# Bidirectional_Amp.net
KiCad netlist of a schematic drawn in EAGLE
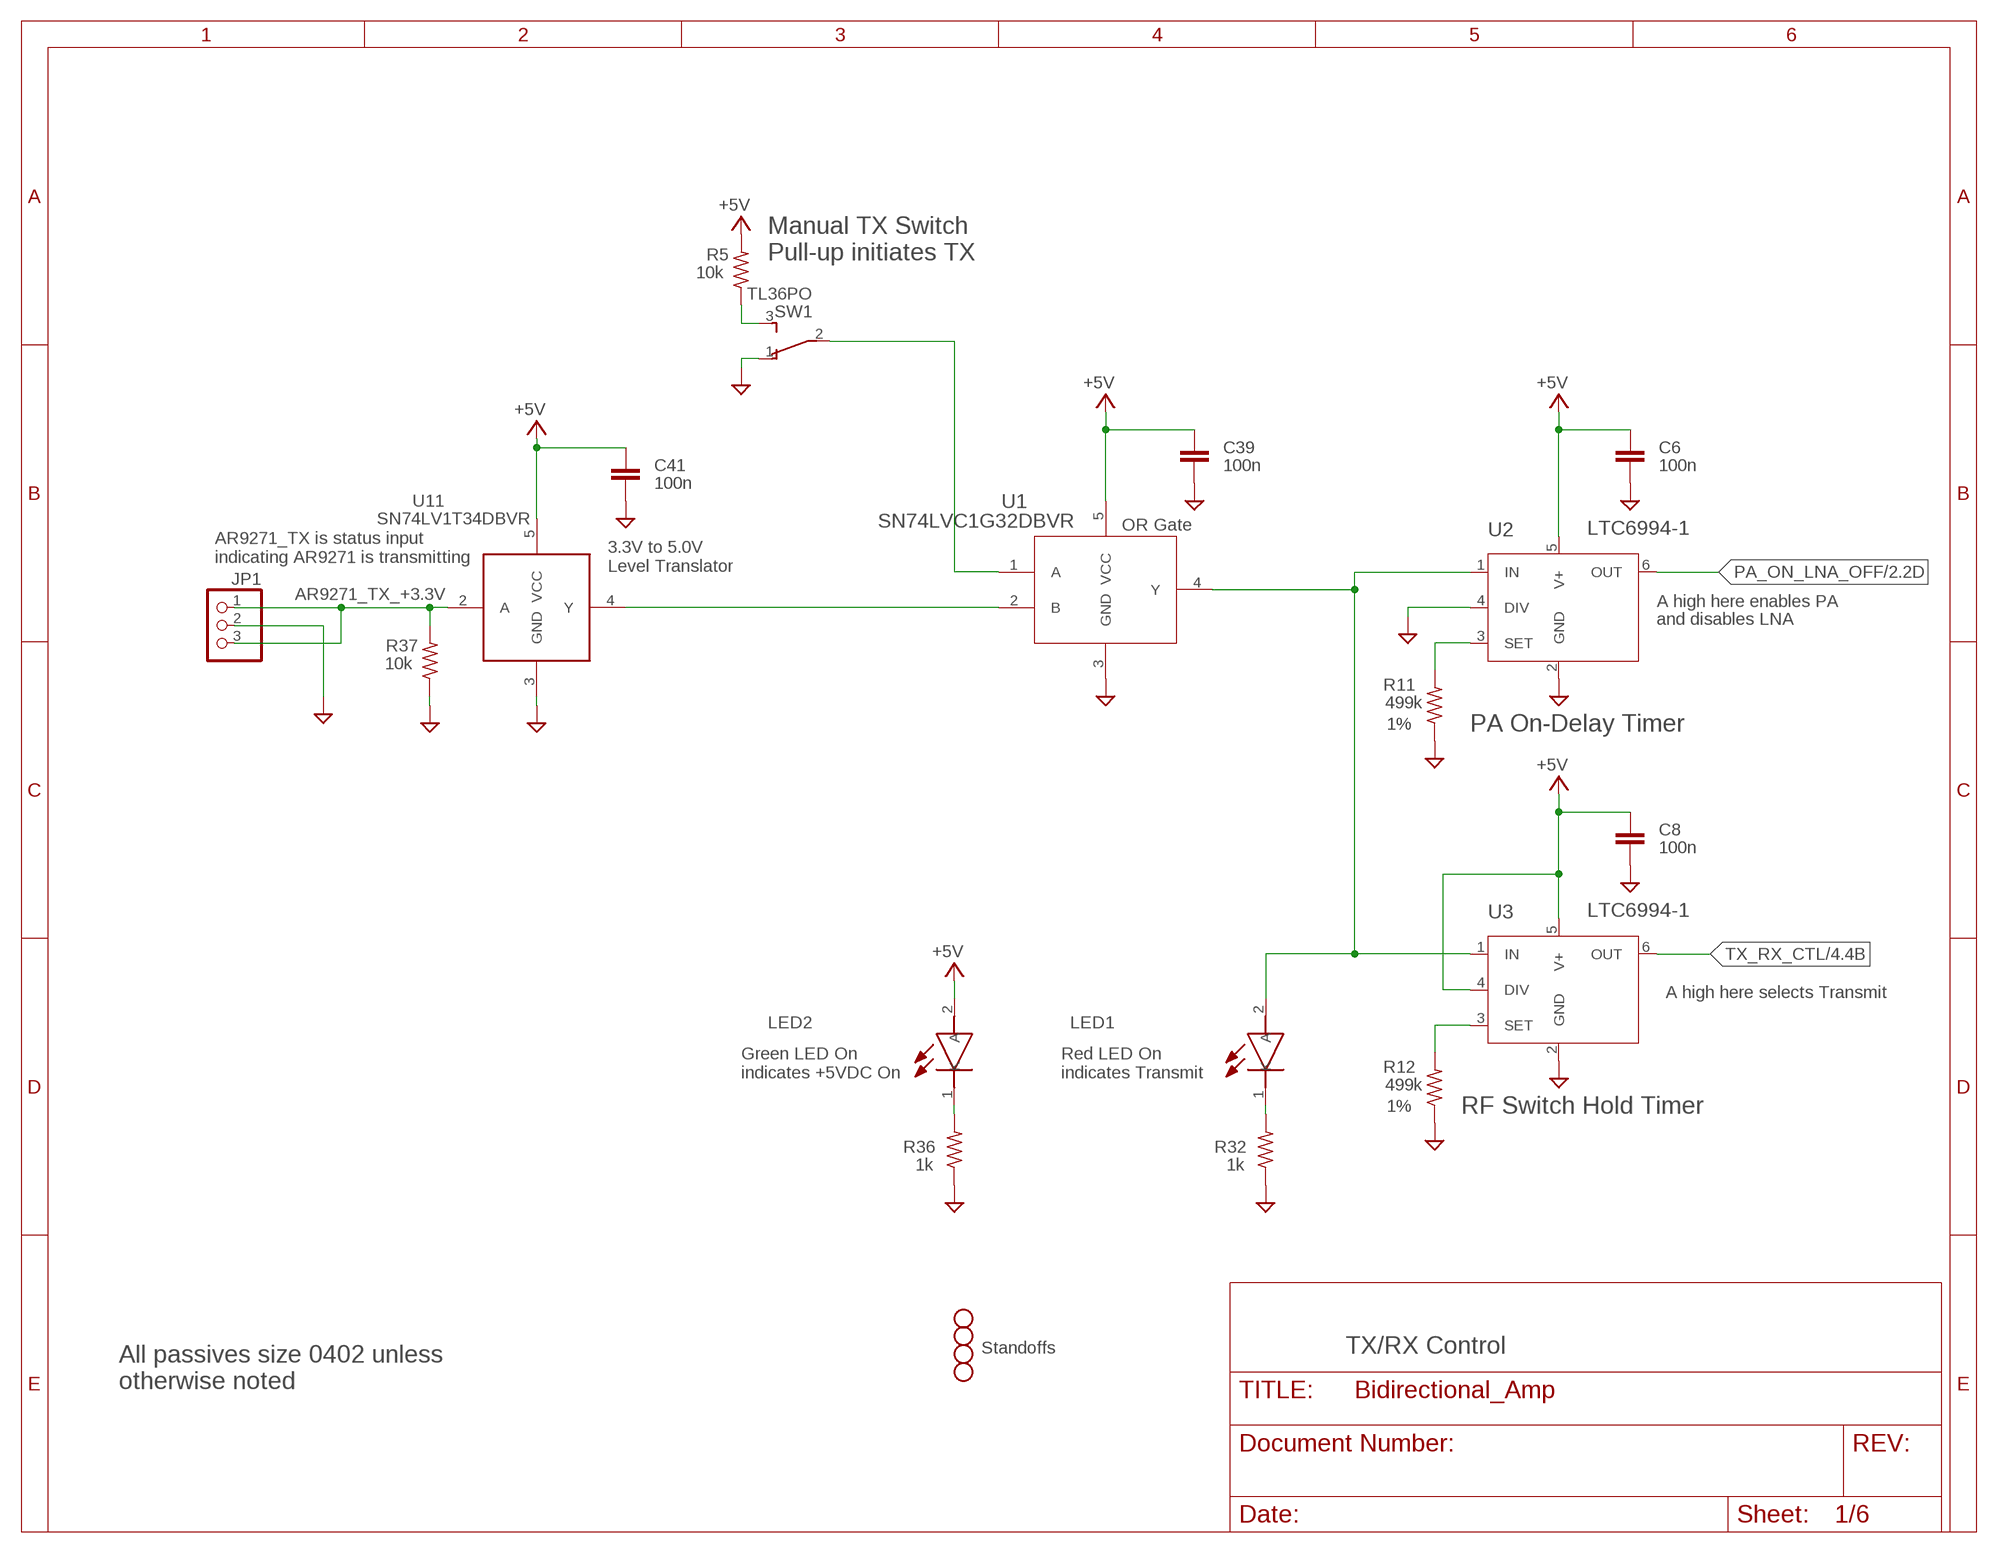
[diagram p0: schematic, sheet 1]
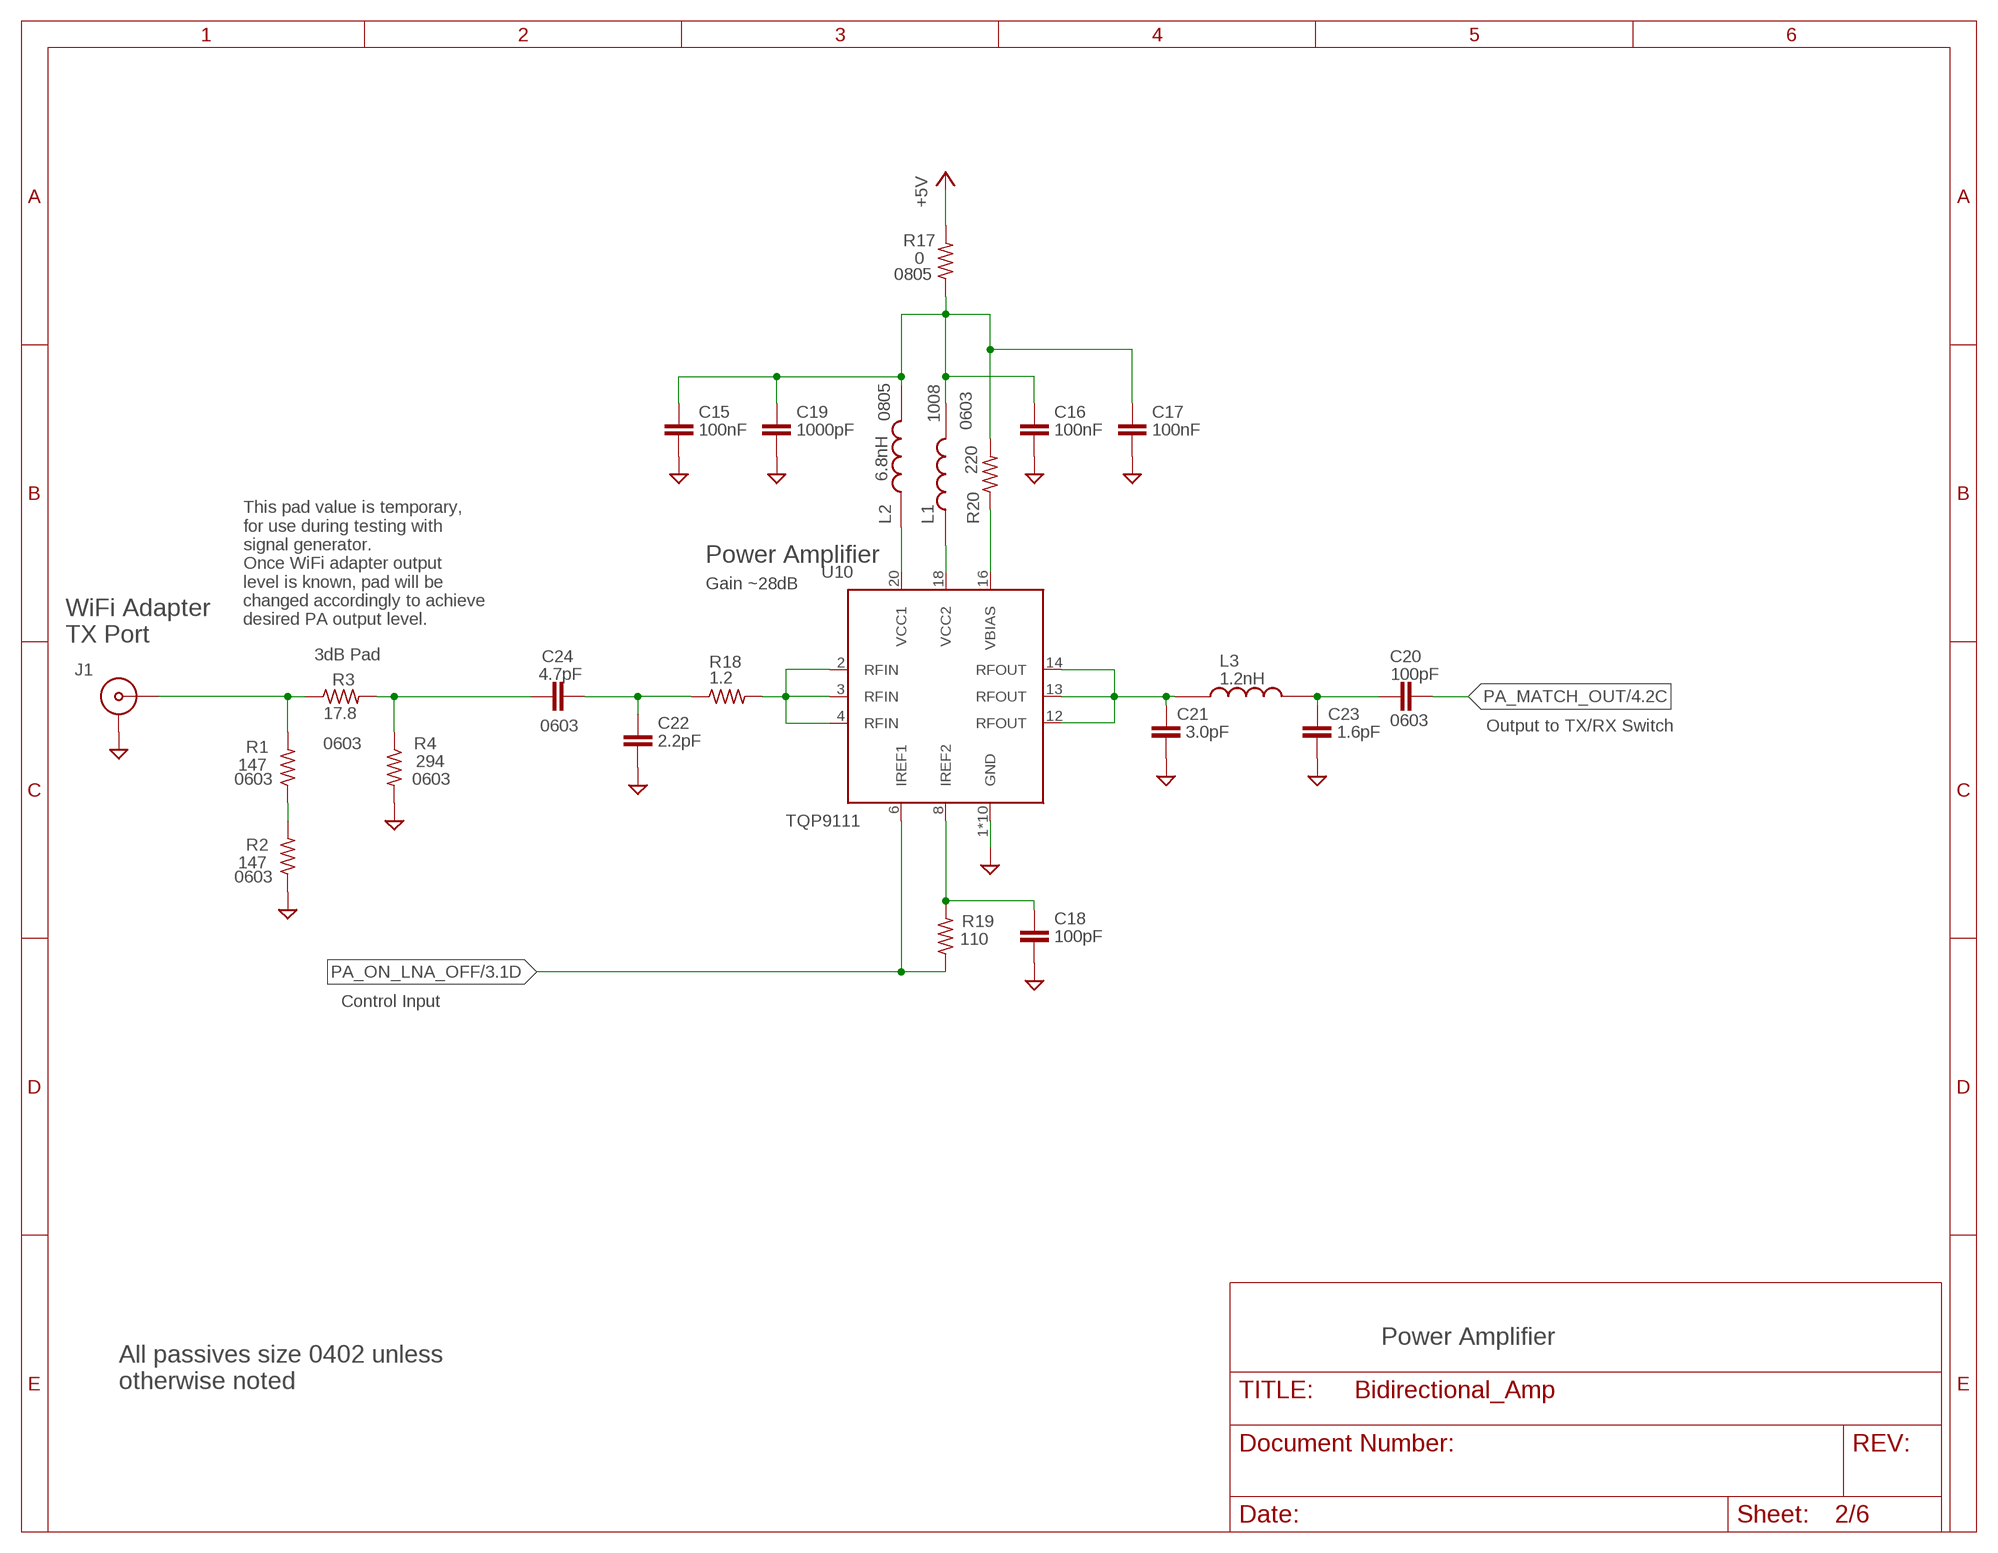
[diagram p1: schematic, sheet 2]
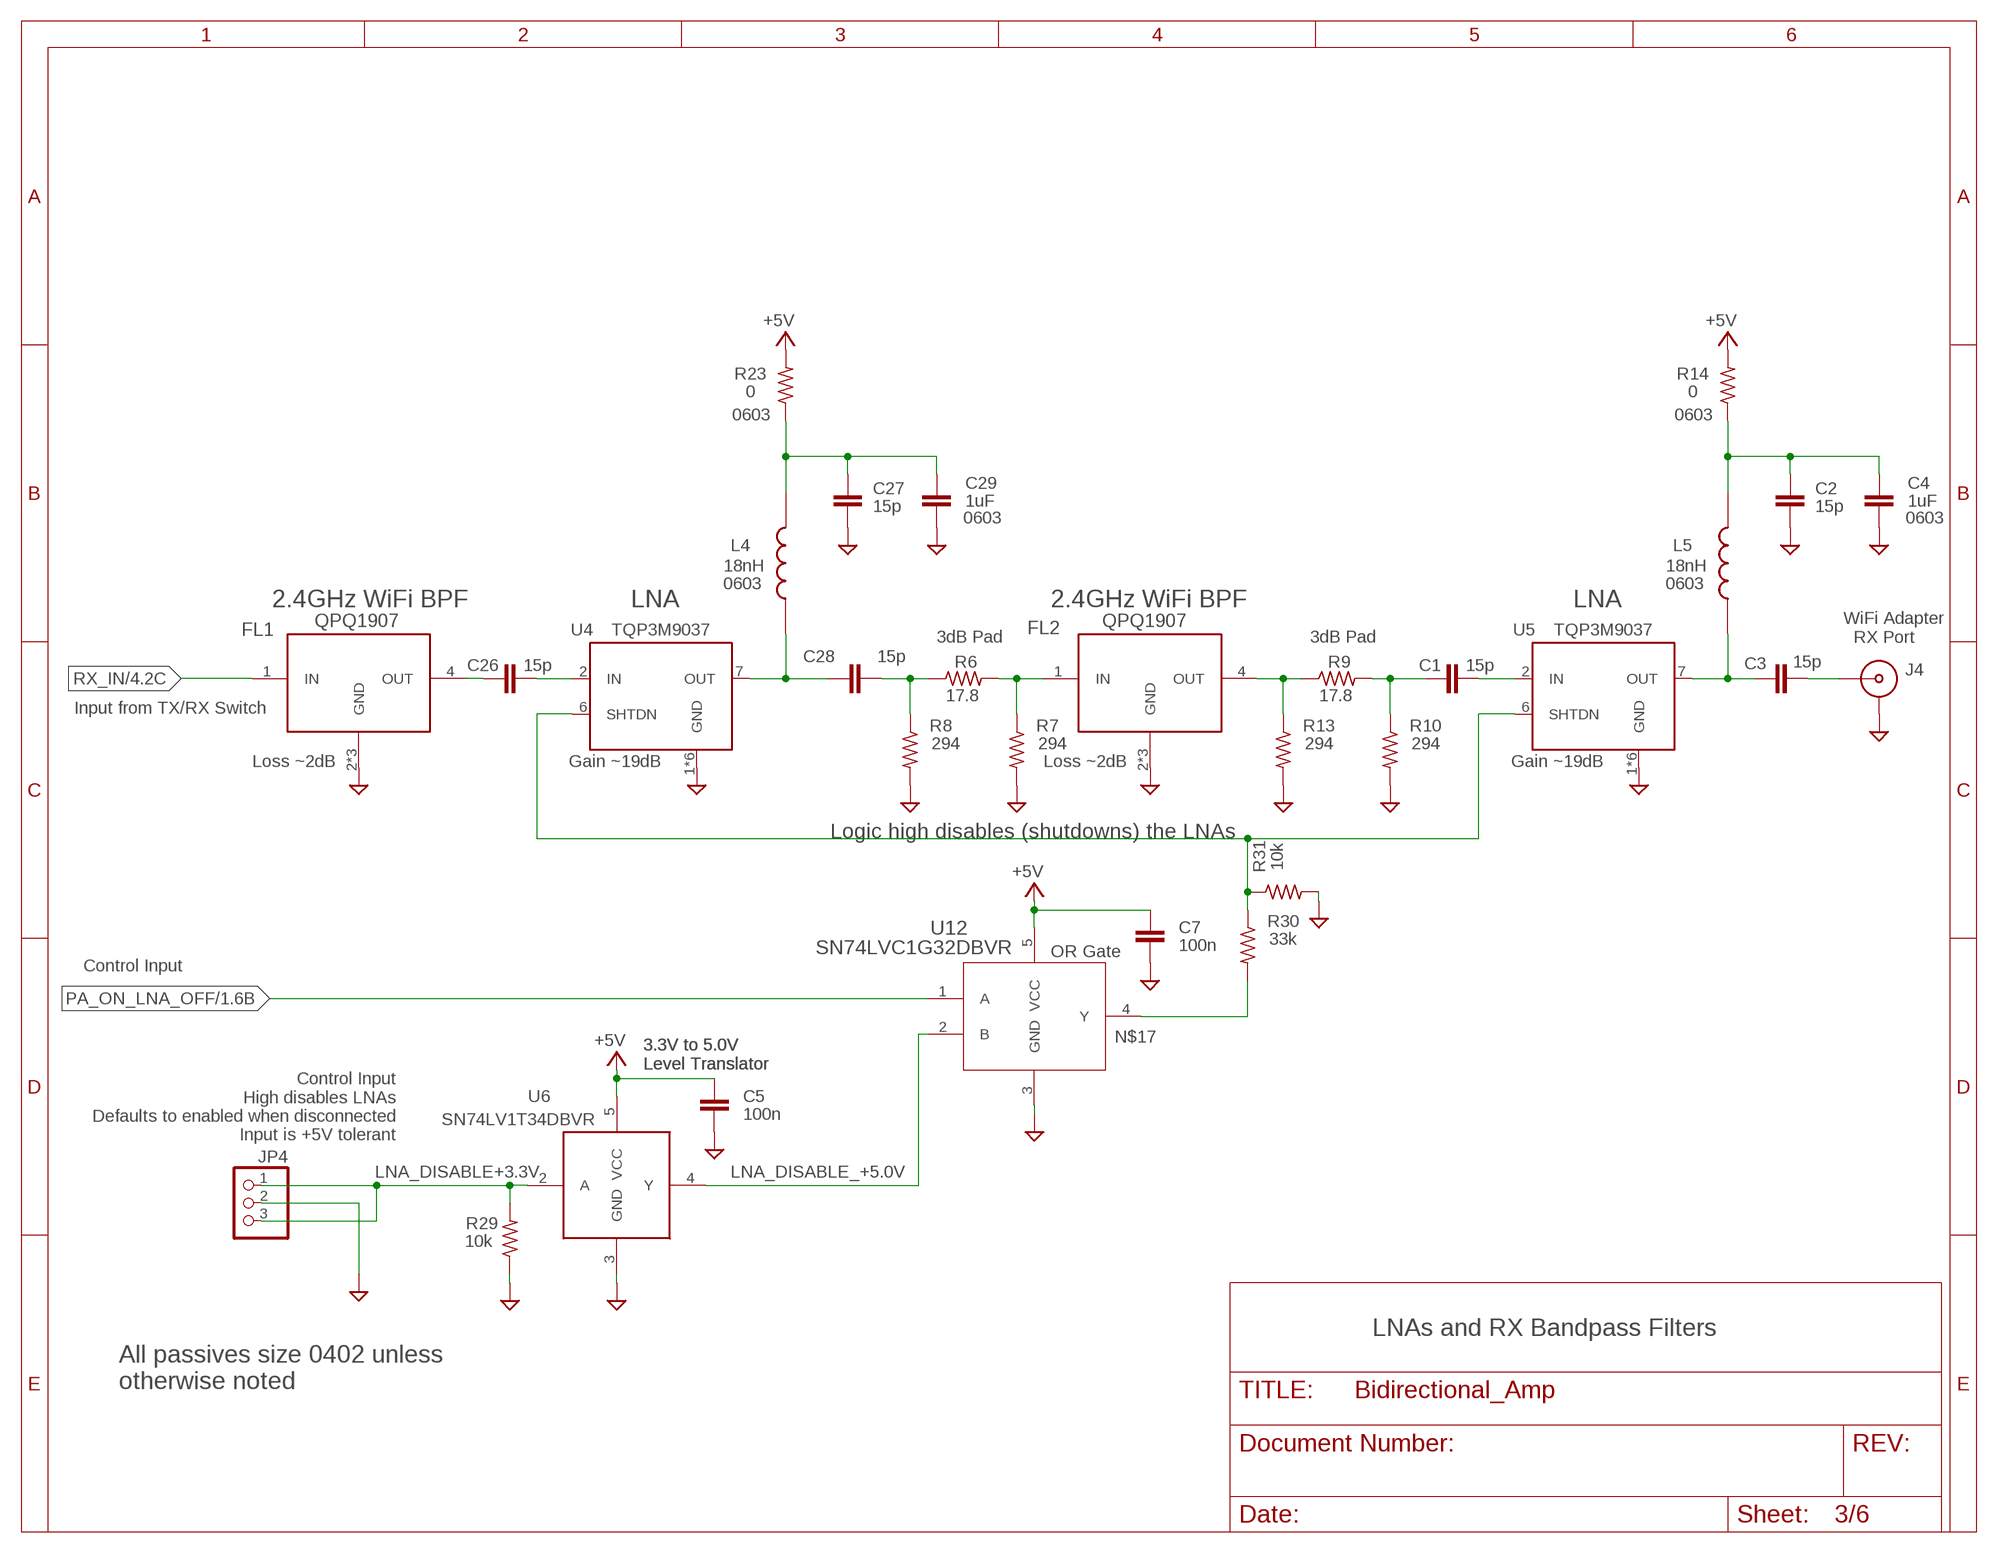
[diagram p2: schematic, sheet 3]
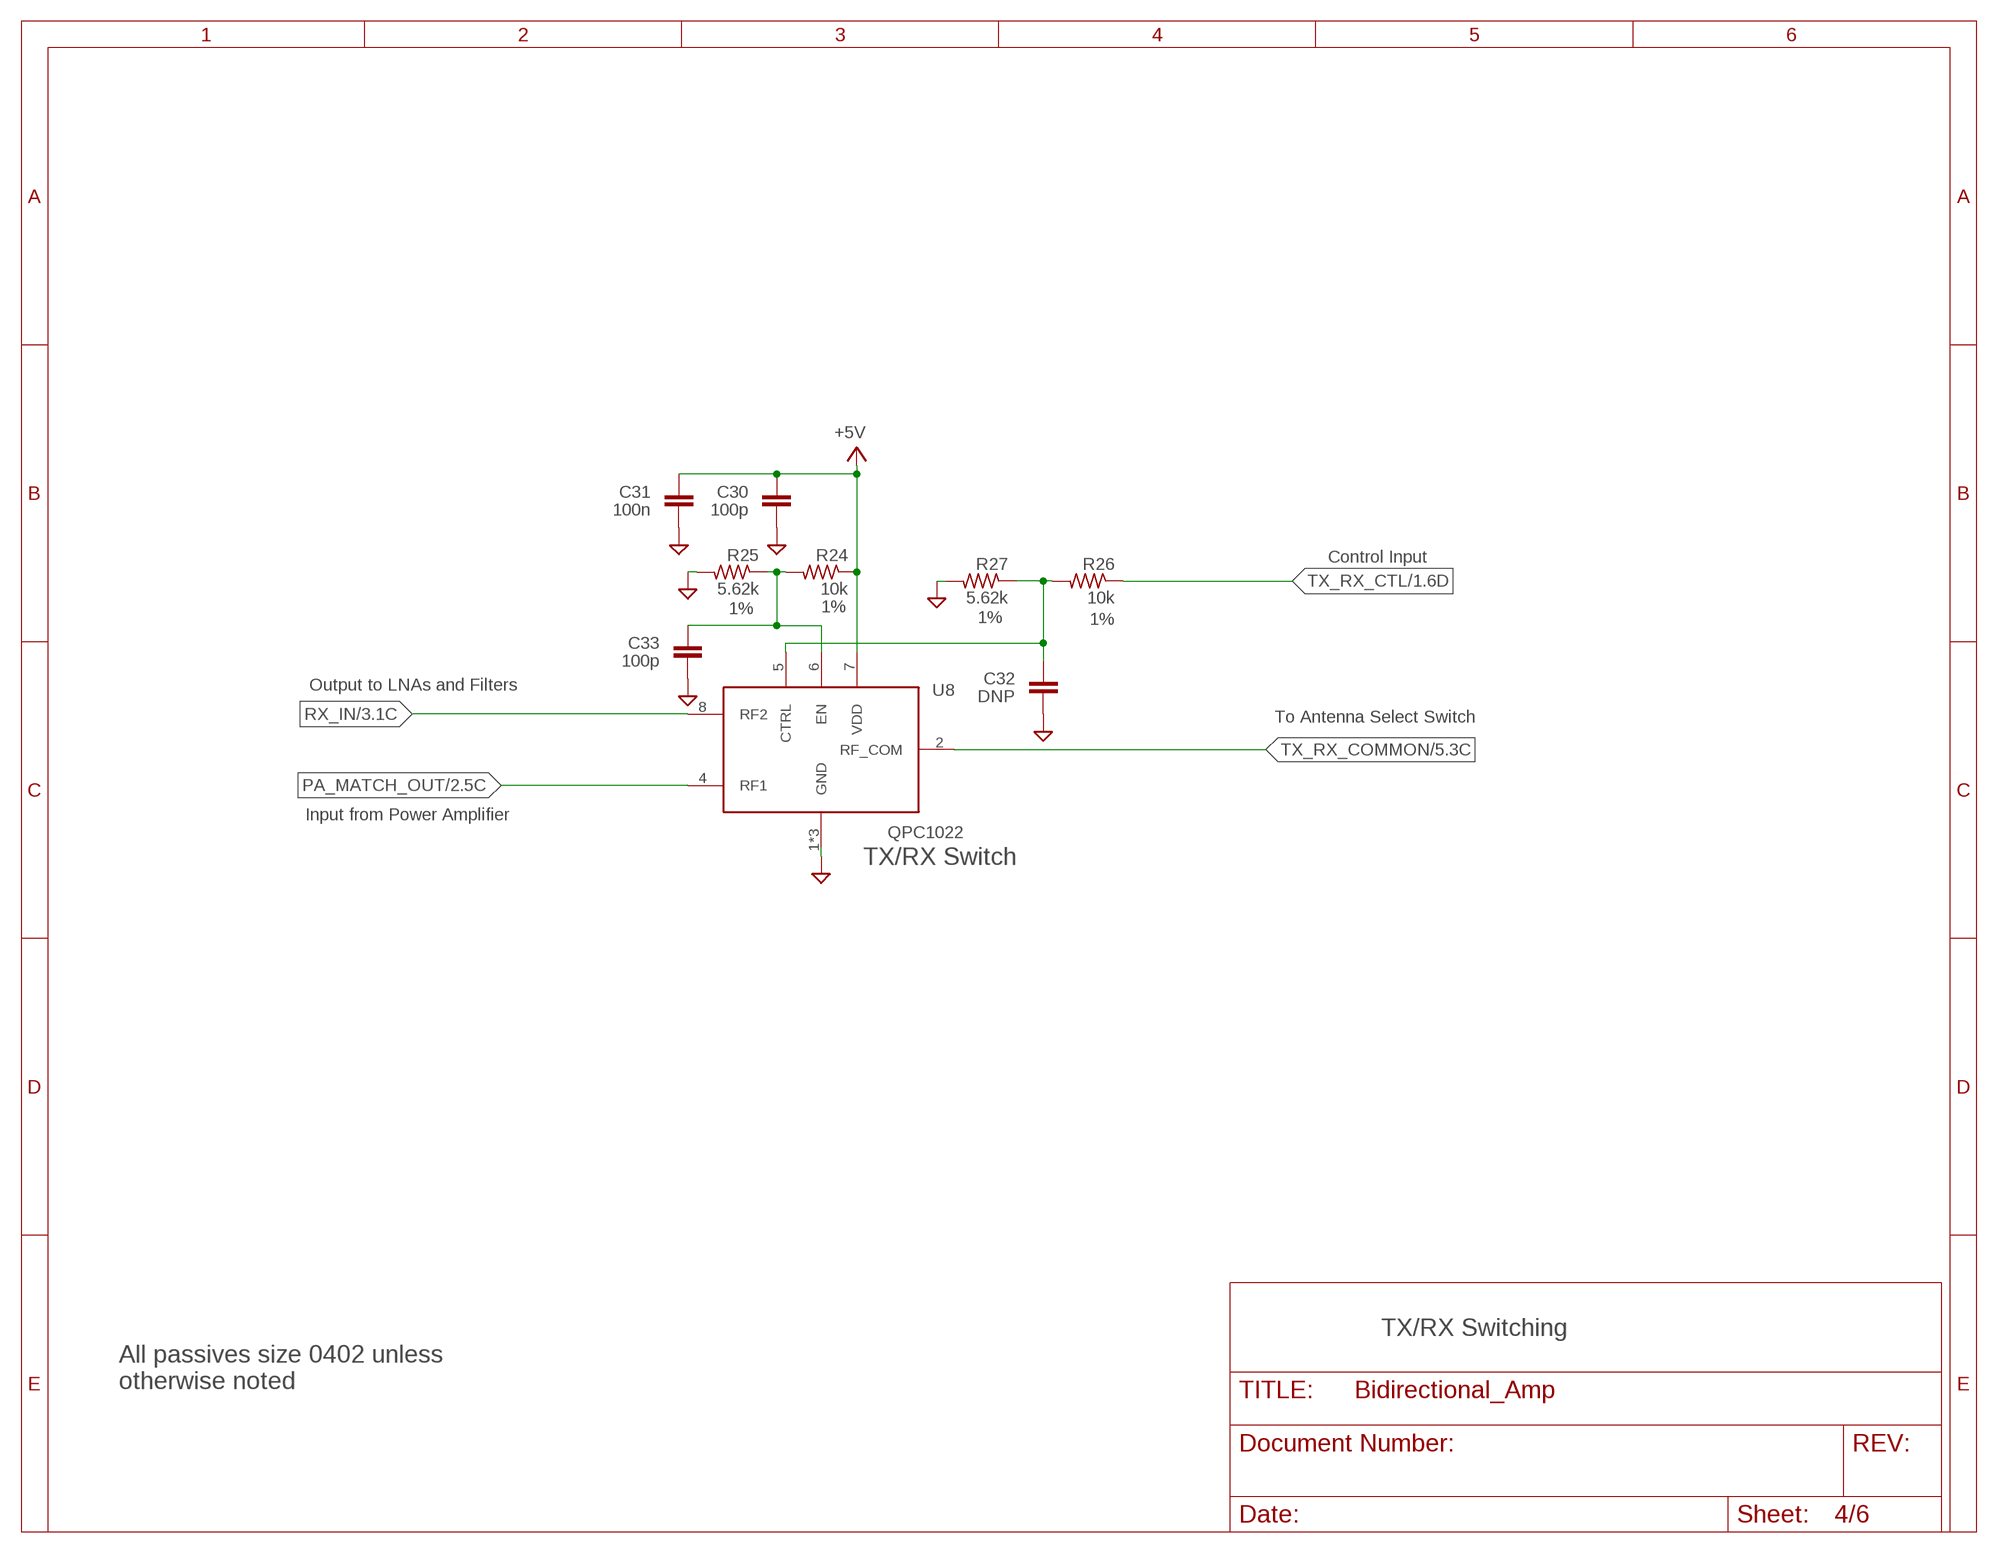
[diagram p3: schematic, sheet 4]
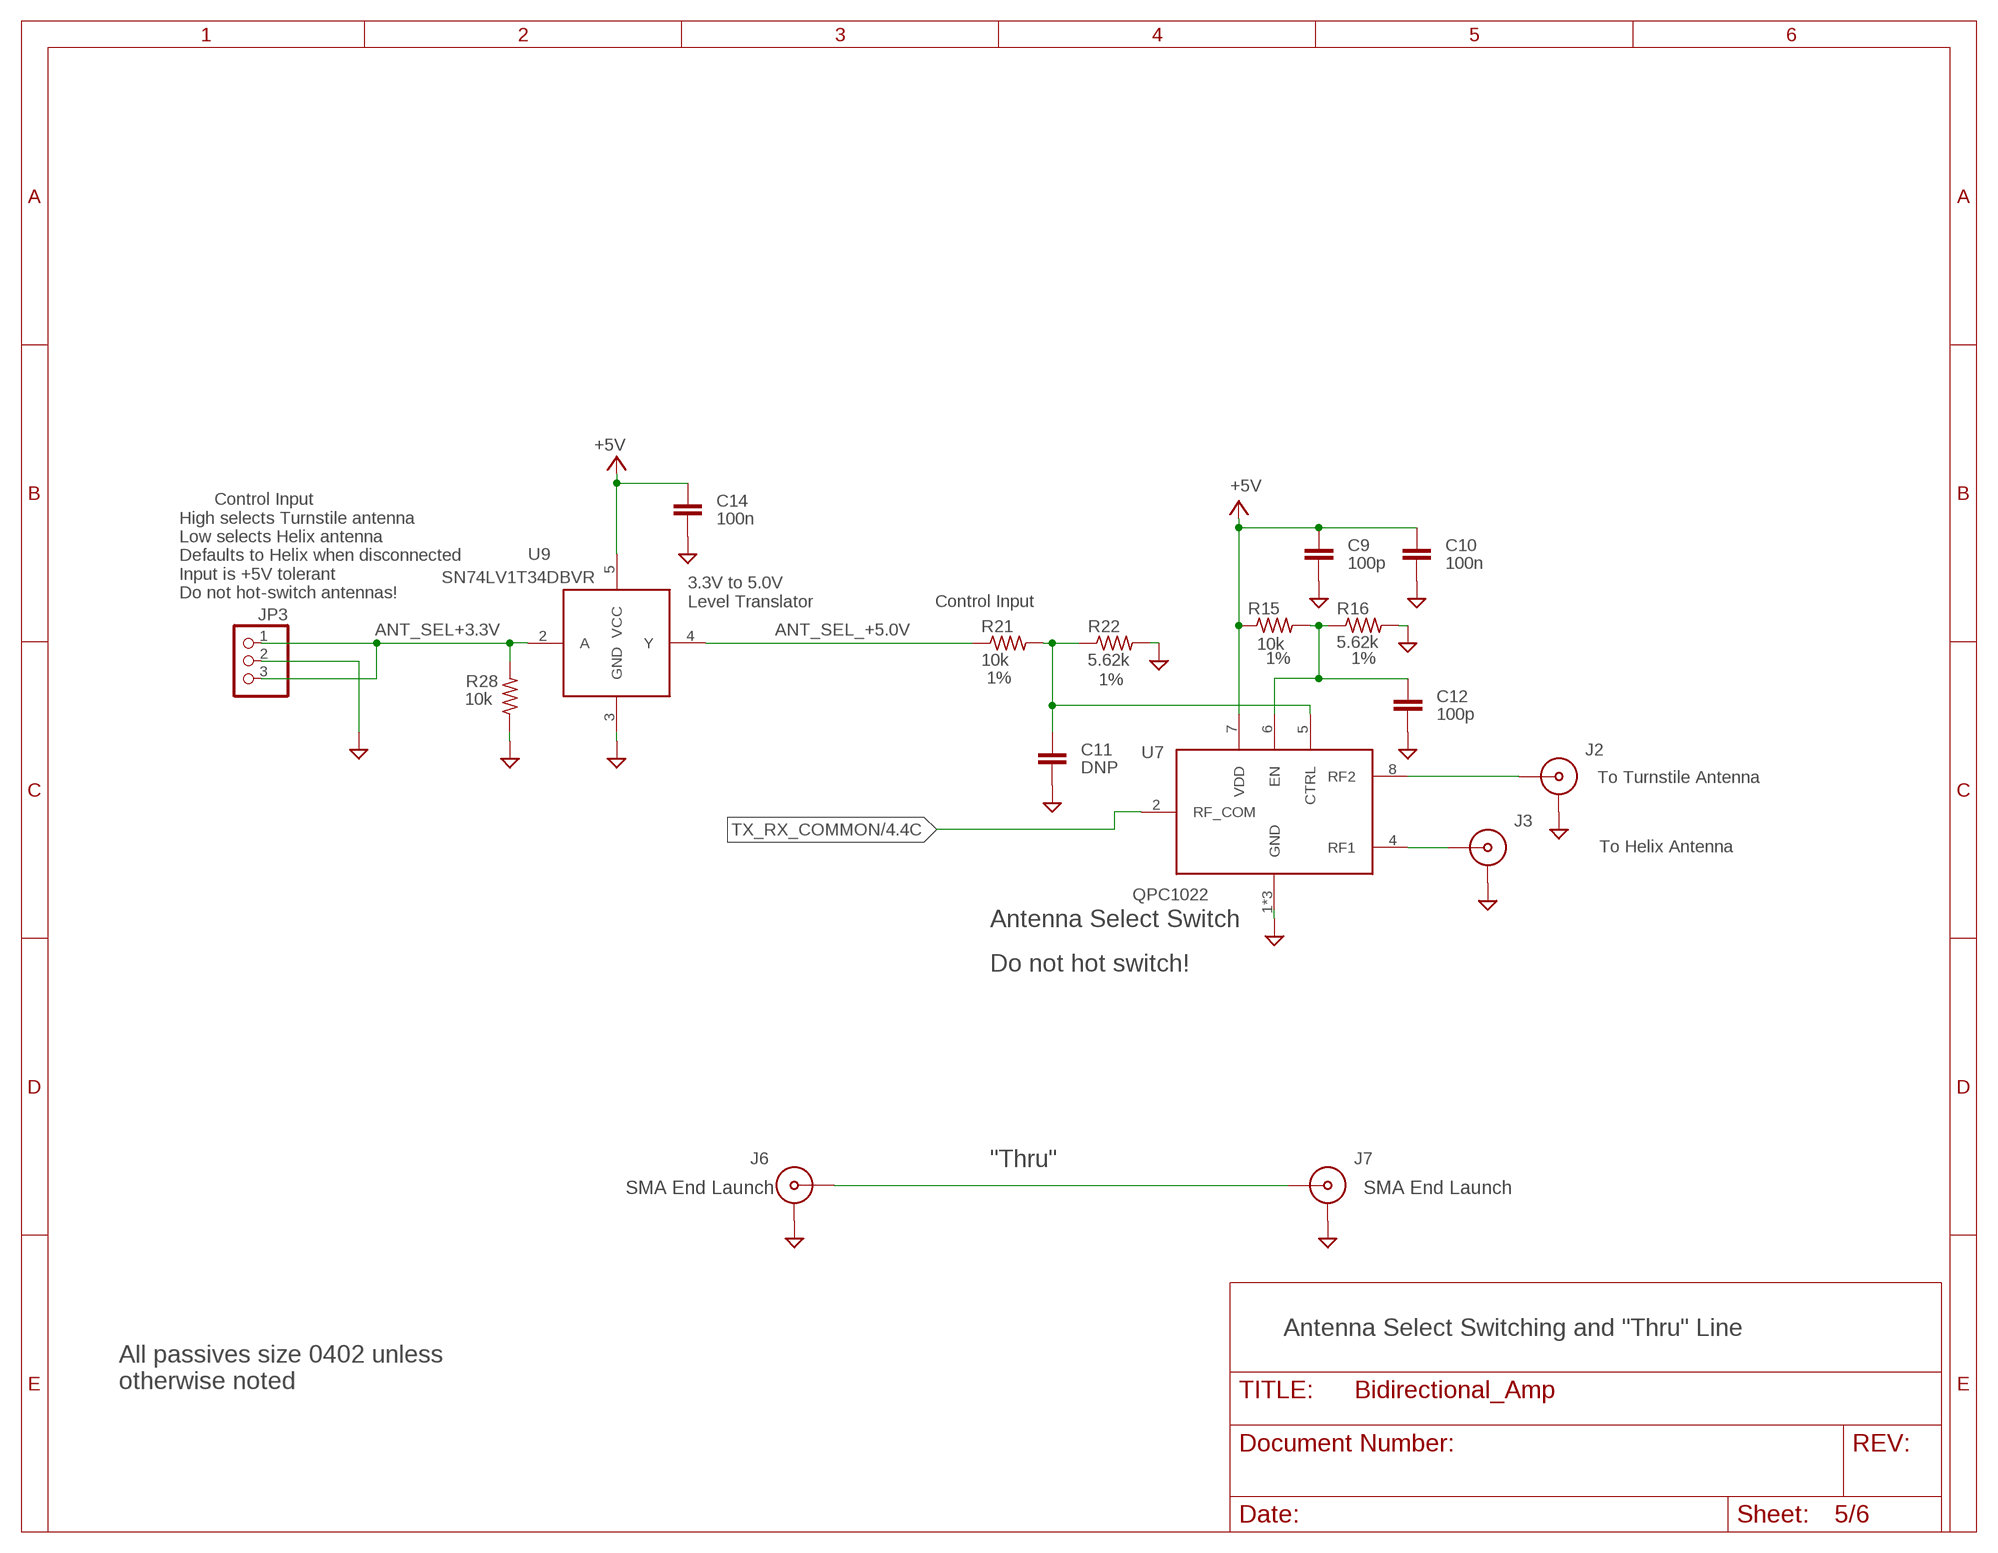
[diagram p4: schematic, sheet 5]
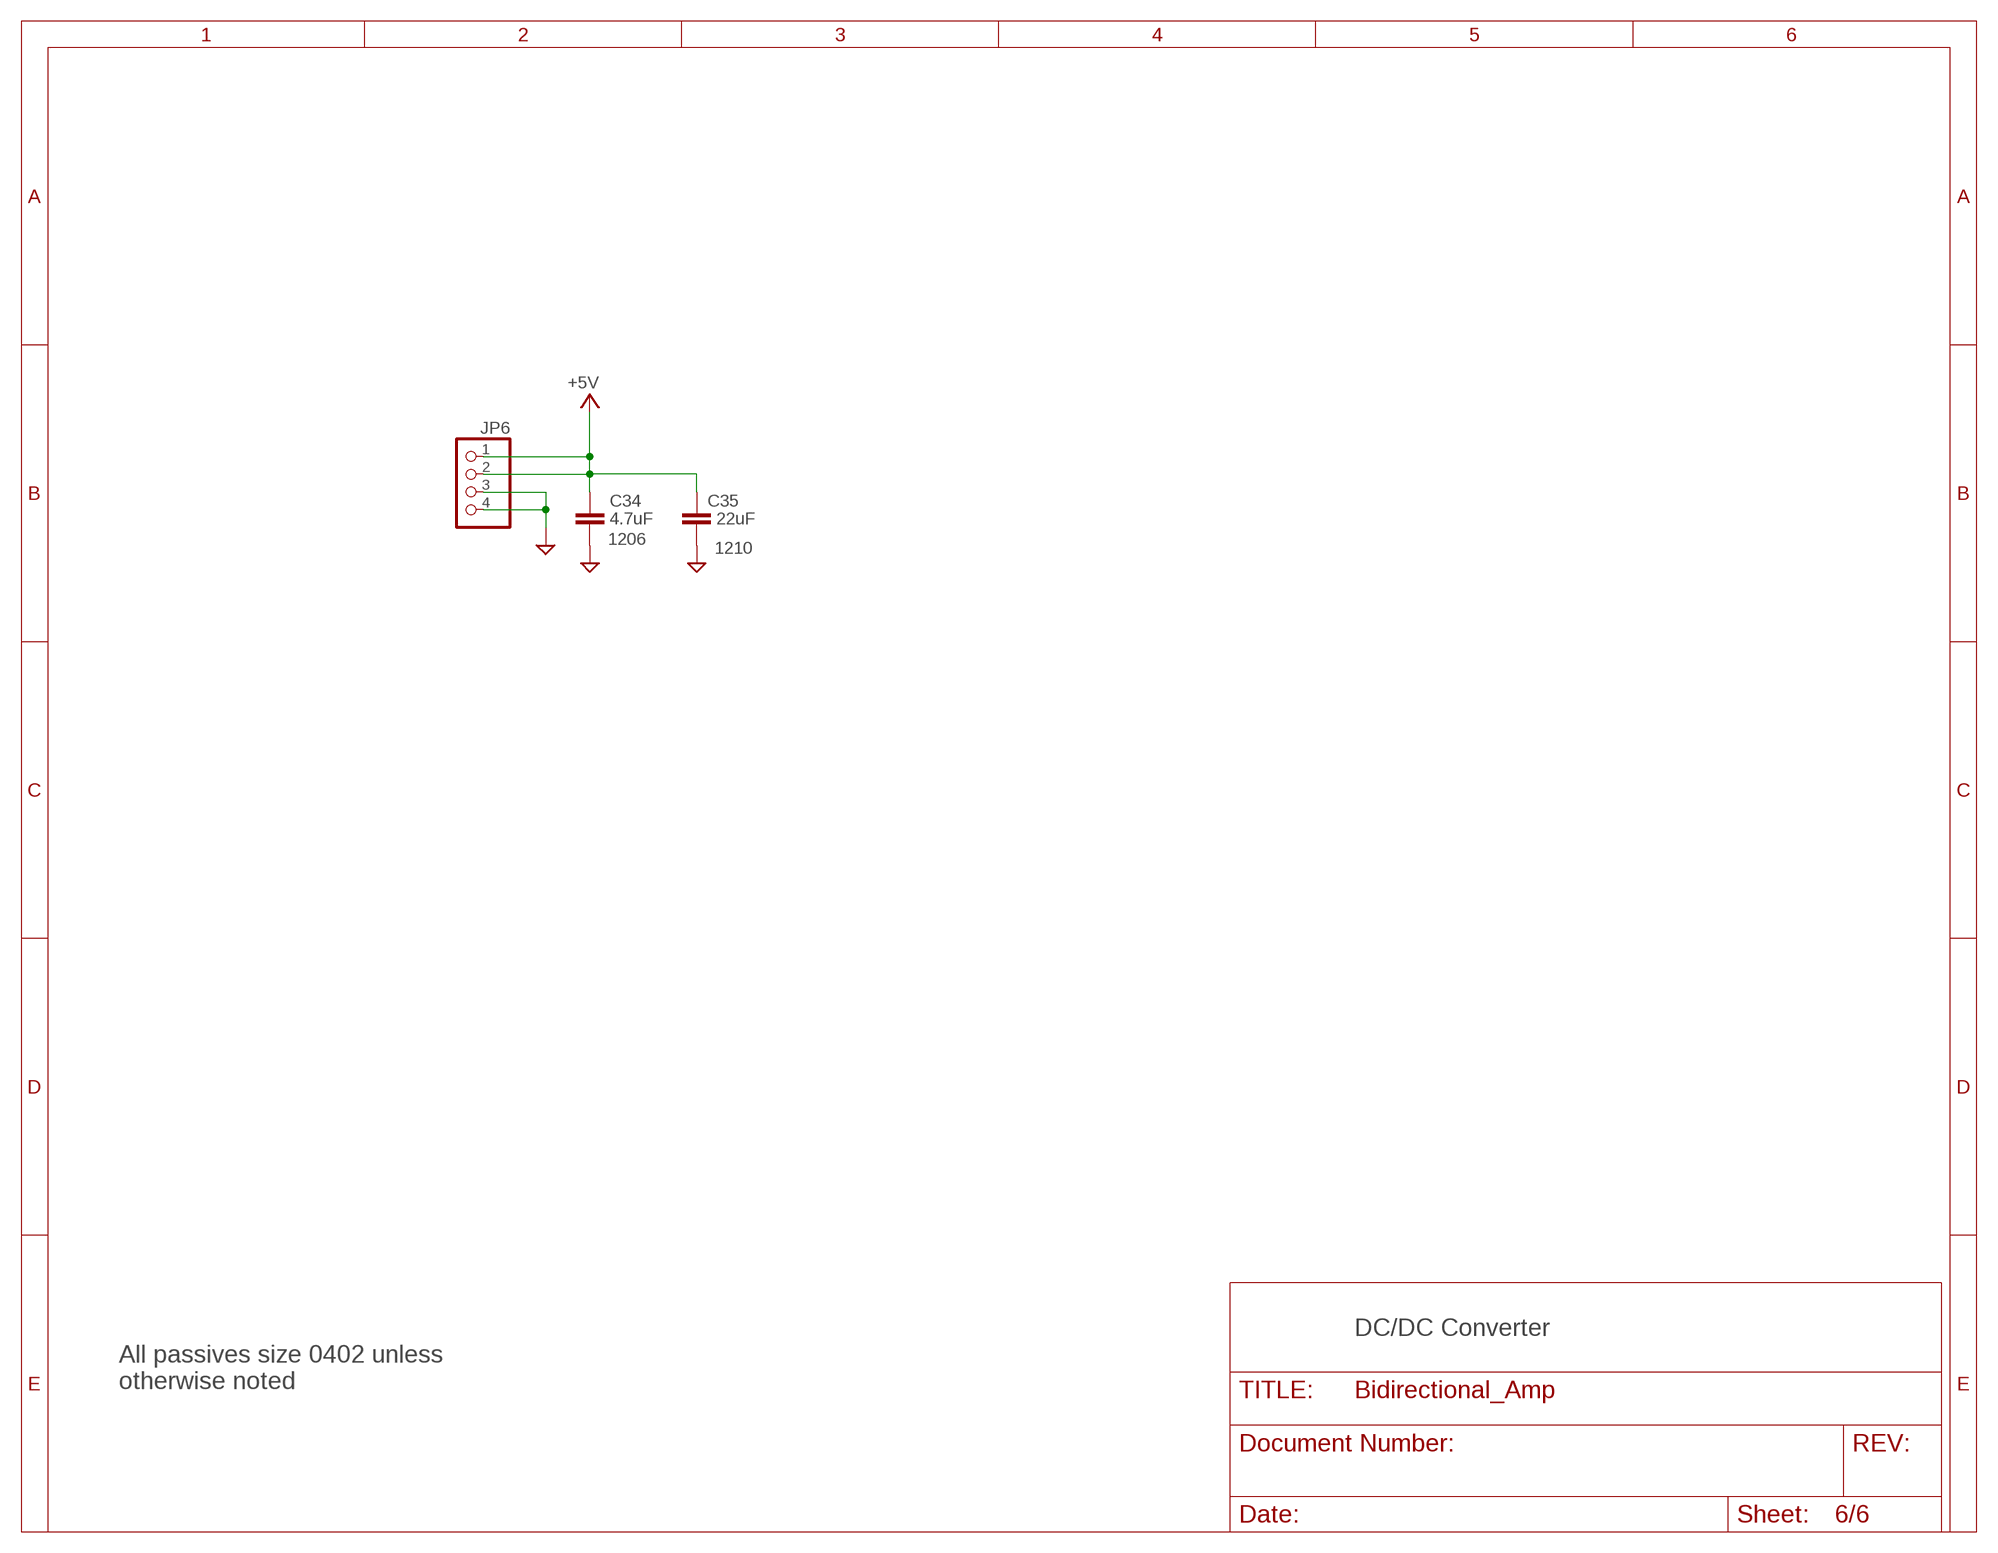
[diagram p5: schematic, sheet 6]

(export (version "E")
  (design (tool "Eeschema 10.0.6"))
  (components
    (comp (ref "C34")
      (value "4.7uF")
      (footprint "eagle-import:C1206")
      (fields
        (field (name "MFR") "Murata")
        (field (name "MPN") "GCJ31CR71C475KA01L")
        (field (name "VOLTAGE") "16V")
      )
      (libsource (lib "eagle-import") (part "rcl_334_C-EUC1206"))
    )
    (comp (ref "C35")
      (value "22uF")
      (footprint "eagle-import:C1210")
      (fields (field (name "MFR") "Murata") (field (name "MPN") "GCJ32ER71C226KE01L"))
      (libsource (lib "eagle-import") (part "rcl_334_C-EUC1210"))
    )
    (comp (ref "JP6")
      (value "PINHD-1X4")
      (footprint "eagle-import:1X04")
      (libsource (lib "eagle-import") (part "PINHD-1X4"))
    )
    (comp (ref "C1")
      (value "15p")
      (footprint "eagle-import:.0402-C-NOSILK")
      (fields (field (name "MFR") "Murata") (field (name "MPN") "GJM1555C1H150JB01D "))
      (libsource (lib "eagle-import") (part "C-EU0402-C-NOSILK"))
    )
    (comp (ref "C2")
      (value "15p")
      (footprint "eagle-import:.0402-B-NOSILK")
      (fields (field (name "MFR") "Murata") (field (name "MPN") "GJM1555C1H150JB01D "))
      (libsource (lib "eagle-import") (part "C-EU0402-B-NOSILK"))
    )
    (comp (ref "C3")
      (value "15p")
      (footprint "eagle-import:.0402-C-NOSILK")
      (fields (field (name "MFR") "Murata") (field (name "MPN") "GJM1555C1H150JB01D "))
      (libsource (lib "eagle-import") (part "C-EU0402-C-NOSILK"))
    )
    (comp (ref "C4")
      (value "1uF")
      (footprint "eagle-import:.0603-B-NOSILK")
      (fields (field (name "MFR") "KEMET") (field (name "MPN") "C0603X105M4RACAUTO "))
      (libsource (lib "eagle-import") (part "C-EU0603-B-NOSILK"))
    )
    (comp (ref "C5")
      (value "100n")
      (footprint "eagle-import:.0402-B-NOSILK")
      (fields (field (name "MFR") "TDK Corporation") (field (name "MPN") "CGA2B1X7R1C104K050BC"))
      (libsource (lib "eagle-import") (part "C-EU0402-B-NOSILK"))
    )
    (comp (ref "C7")
      (value "100n")
      (footprint "eagle-import:.0402-B-NOSILK")
      (fields (field (name "MFR") "TDK") (field (name "MPN") "CGA2B1X7R1C104K050BC"))
      (libsource (lib "eagle-import") (part "C-EU0402-B-NOSILK"))
    )
    (comp (ref "C26")
      (value "15p")
      (footprint "eagle-import:.0402-C-NOSILK")
      (fields (field (name "MFR") "Murata") (field (name "MPN") "GJM1555C1H150JB01D "))
      (libsource (lib "eagle-import") (part "C-EU0402-C-NOSILK"))
    )
    (comp (ref "C27")
      (value "15p")
      (footprint "eagle-import:.0402-B-NOSILK")
      (fields (field (name "MFR") "Murata") (field (name "MPN") "GJM1555C1H150JB01D "))
      (libsource (lib "eagle-import") (part "C-EU0402-B-NOSILK"))
    )
    (comp (ref "C28")
      (value "15p")
      (footprint "eagle-import:.0402-C-NOSILK")
      (fields (field (name "MFR") "Murata") (field (name "MPN") "GJM1555C1H150JB01D "))
      (libsource (lib "eagle-import") (part "C-EU0402-C-NOSILK"))
    )
    (comp (ref "C29")
      (value "1uF")
      (footprint "eagle-import:.0603-B-NOSILK")
      (fields (field (name "MFR") "KEMET") (field (name "MPN") "C0603X105M4RACAUTO "))
      (libsource (lib "eagle-import") (part "C-EU0603-B-NOSILK"))
    )
    (comp (ref "FL1")
      (value "QPQ1907")
      (footprint "eagle-import:FIL_B39162B9417K610")
      (fields (field (name "MFR") "Qorvo") (field (name "MPN") "885071-A") (field (name "MPN_1") "QPQ1907"))
      (libsource (lib "eagle-import") (part "QPQ1907"))
    )
    (comp (ref "FL2")
      (value "QPQ1907")
      (footprint "eagle-import:FIL_B39162B9417K610")
      (fields (field (name "MFR") "Qorvo") (field (name "MPN") "885071-A") (field (name "MPN_1") "QPQ1907"))
      (libsource (lib "eagle-import") (part "QPQ1907"))
    )
    (comp (ref "J4")
      (value "142-0701-851_ALT")
      (footprint "eagle-import:142-0701-851")
      (fields (field (name "MFR") "Cinch") (field (name "MPN") "142-0701-851"))
      (libsource (lib "eagle-import") (part "142-0701-851_ALT"))
    )
    (comp (ref "JP4")
      (value "PINHD-1X3")
      (footprint "eagle-import:1X03")
      (fields (field (name "MFR") "Molex") (field (name "MPN") "22-23-2031"))
      (libsource (lib "eagle-import") (part "PINHD-1X3"))
    )
    (comp (ref "L4")
      (value "68nH")
      (footprint "eagle-import:0603CS-68NXJLW")
      (fields
        (field (name "MFR") "COILCRAFT")
        (field (name "MPN") "0603CS-68NXJLW")
        (field (name "MPN_1") "0603CS-18NXJLW")
      )
      (libsource (lib "eagle-import") (part "0603CS-68NXJLW"))
    )
    (comp (ref "L5")
      (value "68nH")
      (footprint "eagle-import:0603CS-68NXJLW")
      (fields
        (field (name "MFR") "COILCRAFT")
        (field (name "MPN") "0603CS-68NXJLW")
        (field (name "MPN_1") "0603CS-18NXJLW")
      )
      (libsource (lib "eagle-import") (part "0603CS-68NXJLW"))
    )
    (comp (ref "R6")
      (value "17.8")
      (footprint "eagle-import:.0402-C-NOSILK")
      (fields (field (name "MFR") "Panasonic") (field (name "MPN") "ERJ-2RKF17R8X"))
      (libsource (lib "eagle-import") (part "R-US_0402-C-NOSILK"))
    )
    (comp (ref "R7")
      (value "294")
      (footprint "eagle-import:.0402-C-NOSILK")
      (fields (field (name "MFR") "Panasonic") (field (name "MPN") "ERJ-2RKF2940X"))
      (libsource (lib "eagle-import") (part "R-US_0402-C-NOSILK"))
    )
    (comp (ref "R8")
      (value "294")
      (footprint "eagle-import:.0402-C-NOSILK")
      (fields (field (name "MFR") "Panasonic") (field (name "MPN") "ERJ-2RKF2940X"))
      (libsource (lib "eagle-import") (part "R-US_0402-C-NOSILK"))
    )
    (comp (ref "R9")
      (value "17.8")
      (footprint "eagle-import:.0402-C-NOSILK")
      (fields (field (name "MFR") "Panasonic") (field (name "MPN") "ERJ-2RKF17R8X"))
      (libsource (lib "eagle-import") (part "R-US_0402-C-NOSILK"))
    )
    (comp (ref "R10")
      (value "294")
      (footprint "eagle-import:.0402-C-NOSILK")
      (fields (field (name "MFR") "Panasonic") (field (name "MPN") "ERJ-2RKF2940X"))
      (libsource (lib "eagle-import") (part "R-US_0402-C-NOSILK"))
    )
    (comp (ref "R13")
      (value "294")
      (footprint "eagle-import:.0402-C-NOSILK")
      (fields (field (name "MFR") "Panasonic") (field (name "MPN") "ERJ-2RKF2940X"))
      (libsource (lib "eagle-import") (part "R-US_0402-C-NOSILK"))
    )
    (comp (ref "R14")
      (value "0")
      (footprint "eagle-import:.0603-B-NOSILK")
      (fields (field (name "MFR") "Panasonic") (field (name "MPN") "ERJ-3GEY0R00V"))
      (libsource (lib "eagle-import") (part "R-US_0603-B-NOSILK"))
    )
    (comp (ref "R23")
      (value "0")
      (footprint "eagle-import:.0603-B-NOSILK")
      (fields (field (name "MFR") "Panasonic") (field (name "MPN") "ERJ-3GEY0R00V"))
      (libsource (lib "eagle-import") (part "R-US_0603-B-NOSILK"))
    )
    (comp (ref "R29")
      (value "10k")
      (footprint "eagle-import:.0402-B-NOSILK")
      (fields (field (name "MFR") "Panasonic") (field (name "MPN") "ERJ-2GEJ103X"))
      (libsource (lib "eagle-import") (part "R-US_0402-B-NOSILK"))
    )
    (comp (ref "R30")
      (value "33k")
      (footprint "eagle-import:.0402-B-NOSILK")
      (fields (field (name "MFR") "Panasonic") (field (name "MPN") "ERJ-2RKF2940X"))
      (libsource (lib "eagle-import") (part "R-US_0402-B-NOSILK"))
    )
    (comp (ref "R31")
      (value "10k")
      (footprint "eagle-import:.0402-B-NOSILK")
      (fields (field (name "MFR") "Panasonic") (field (name "MPN") "ERJ-2RKF2940X"))
      (libsource (lib "eagle-import") (part "R-US_0402-B-NOSILK"))
    )
    (comp (ref "U4")
      (value "TQP3M9037")
      (footprint "eagle-import:DFN8-2X2-WITH-PAD")
      (fields (field (name "MFR") "Qorvo") (field (name "MPN") "TQP3M9037 "))
      (libsource (lib "eagle-import") (part "TQP3M903X"))
    )
    (comp (ref "U5")
      (value "TQP3M9037")
      (footprint "eagle-import:DFN8-2X2-WITH-PAD")
      (fields (field (name "MFR") "Qorvo") (field (name "MPN") "TQP3M9037 "))
      (libsource (lib "eagle-import") (part "TQP3M903X"))
    )
    (comp (ref "U6")
      (value "SN74LV1T34DBVR")
      (footprint "eagle-import:SOT95P280X145-5N")
      (fields (field (name "MFR") "Texas Instruments"))
      (libsource (lib "eagle-import") (part "SN74LV1T34DBVR"))
    )
    (comp (ref "U12")
      (value "SN74LVC1G32DBVR")
      (footprint "eagle-import:DBV5")
      (fields (field (name "MFR") "Texas Instruments"))
      (libsource (lib "eagle-import") (part "SN74LVC1G32DBVR"))
    )
    (comp (ref "C9")
      (value "100p")
      (footprint "eagle-import:.0402-B-NOSILK")
      (fields (field (name "MFR") "Murata") (field (name "MPN") "GCM1555C1H101JA16D "))
      (libsource (lib "eagle-import") (part "C-EU0402-B-NOSILK"))
    )
    (comp (ref "C10")
      (value "100n")
      (footprint "eagle-import:.0402-B-NOSILK")
      (fields (field (name "MFR") "TDK Corporation") (field (name "MPN") "CGA2B1X7R1C104K050BC"))
      (libsource (lib "eagle-import") (part "C-EU0402-B-NOSILK"))
    )
    (comp (ref "C11")
      (value "DNP")
      (footprint "eagle-import:.0402-B-NOSILK")
      (fields (field (name "MPN") "GCM1555C1H101JA16D "))
      (libsource (lib "eagle-import") (part "C-EU0402-B-NOSILK"))
    )
    (comp (ref "C12")
      (value "100p")
      (footprint "eagle-import:.0402-B-NOSILK")
      (fields (field (name "MPN") "GCM1555C1H101JA16D "))
      (libsource (lib "eagle-import") (part "C-EU0402-B-NOSILK"))
    )
    (comp (ref "C14")
      (value "100n")
      (footprint "eagle-import:.0402-B-NOSILK")
      (fields (field (name "MFR") "TDK Corporation") (field (name "MPN") "CGA2B1X7R1C104K050BC"))
      (libsource (lib "eagle-import") (part "C-EU0402-B-NOSILK"))
    )
    (comp (ref "J2")
      (value "142-0701-851_ALT")
      (footprint "eagle-import:142-0701-851")
      (fields (field (name "MFR") "Cinch") (field (name "MPN") "142-0701-851"))
      (libsource (lib "eagle-import") (part "142-0701-851_ALT"))
    )
    (comp (ref "J3")
      (value "142-0701-851_ALT")
      (footprint "eagle-import:142-0701-851")
      (fields (field (name "MFR") "Cinch") (field (name "MPN") "142-0701-851"))
      (libsource (lib "eagle-import") (part "142-0701-851_ALT"))
    )
    (comp (ref "J6")
      (value "142-0701-851_ALT")
      (footprint "eagle-import:142-0701-851")
      (fields (field (name "MFR") "Cinch") (field (name "MPN") "142-0701-851"))
      (libsource (lib "eagle-import") (part "142-0701-851_ALT"))
    )
    (comp (ref "J7")
      (value "142-0701-851_ALT")
      (footprint "eagle-import:142-0701-851")
      (fields (field (name "MFR") "Cinch") (field (name "MPN") "142-0701-851"))
      (libsource (lib "eagle-import") (part "142-0701-851_ALT"))
    )
    (comp (ref "JP3")
      (value "PINHD-1X3")
      (footprint "eagle-import:1X03")
      (fields (field (name "MFR") "Molex") (field (name "MPN") "22-23-2031"))
      (libsource (lib "eagle-import") (part "PINHD-1X3"))
    )
    (comp (ref "R15")
      (value "10k")
      (footprint "eagle-import:.0402-B-NOSILK")
      (fields (field (name "MFR") "Panasonic") (field (name "MPN") "ERJ-2RKF1002X"))
      (libsource (lib "eagle-import") (part "R-US_0402-B-NOSILK"))
    )
    (comp (ref "R16")
      (value "5.62k")
      (footprint "eagle-import:.0402-B-NOSILK")
      (fields (field (name "MFR") "Panasonic") (field (name "MPN") "ERJ-2RKF5621X"))
      (libsource (lib "eagle-import") (part "R-US_0402-B-NOSILK"))
    )
    (comp (ref "R21")
      (value "10k")
      (footprint "eagle-import:.0402-B-NOSILK")
      (fields (field (name "MFR") "Panasonic") (field (name "MPN") "ERJ-2RKF1002X"))
      (libsource (lib "eagle-import") (part "R-US_0402-B-NOSILK"))
    )
    (comp (ref "R22")
      (value "5.62k")
      (footprint "eagle-import:.0402-B-NOSILK")
      (fields (field (name "MFR") "Panasonic") (field (name "MPN") "ERJ-2RKF5621X"))
      (libsource (lib "eagle-import") (part "R-US_0402-B-NOSILK"))
    )
    (comp (ref "R28")
      (value "10k")
      (footprint "eagle-import:.0402-B-NOSILK")
      (fields (field (name "MFR") "Panasonic") (field (name "MPN") "ERJ-2GEJ103X"))
      (libsource (lib "eagle-import") (part "R-US_0402-B-NOSILK"))
    )
    (comp (ref "U7")
      (value "QPC1022")
      (footprint "eagle-import:QPC1022")
      (fields (field (name "MFR") "Qorvo"))
      (libsource (lib "eagle-import") (part "QPC1022"))
    )
    (comp (ref "U9")
      (value "SN74LV1T34DBVR")
      (footprint "eagle-import:SOT95P280X145-5N")
      (fields (field (name "MFR") "Texas Instruments"))
      (libsource (lib "eagle-import") (part "SN74LV1T34DBVR"))
    )
    (comp (ref "C30")
      (value "100p")
      (footprint "eagle-import:.0402-B-NOSILK")
      (fields (field (name "MFR") "Murata") (field (name "MPN") "GCM1555C1H101JA16D "))
      (libsource (lib "eagle-import") (part "C-EU0402-B-NOSILK"))
    )
    (comp (ref "C31")
      (value "100n")
      (footprint "eagle-import:.0402-B-NOSILK")
      (fields (field (name "MFR") "TDK Corporation") (field (name "MPN") "CGA2B1X7R1C104K050BC"))
      (libsource (lib "eagle-import") (part "C-EU0402-B-NOSILK"))
    )
    (comp (ref "C32")
      (value "DNP")
      (footprint "eagle-import:.0402-B-NOSILK")
      (libsource (lib "eagle-import") (part "C-EU0402-B-NOSILK"))
    )
    (comp (ref "C33")
      (value "100p")
      (footprint "eagle-import:.0402-B-NOSILK")
      (fields (field (name "MFR") "Murata") (field (name "MPN") "GCM1555C1H101JA16D "))
      (libsource (lib "eagle-import") (part "C-EU0402-B-NOSILK"))
    )
    (comp (ref "R24")
      (value "10k")
      (footprint "eagle-import:.0402-B-NOSILK")
      (fields (field (name "MFR") "Panasonic") (field (name "MPN") "ERJ-2RKF1002X"))
      (libsource (lib "eagle-import") (part "R-US_0402-B-NOSILK"))
    )
    (comp (ref "R25")
      (value "5.62k")
      (footprint "eagle-import:.0402-B-NOSILK")
      (fields (field (name "MFR") "Panasonic") (field (name "MPN") "ERJ-2RKF5621X"))
      (libsource (lib "eagle-import") (part "R-US_0402-B-NOSILK"))
    )
    (comp (ref "R26")
      (value "10k")
      (footprint "eagle-import:.0402-B-NOSILK")
      (fields (field (name "MFR") "Panasonic") (field (name "MPN") "ERJ-2RKF1002X"))
      (libsource (lib "eagle-import") (part "R-US_0402-B-NOSILK"))
    )
    (comp (ref "R27")
      (value "5.62k")
      (footprint "eagle-import:.0402-B-NOSILK")
      (fields (field (name "MFR") "Panasonic") (field (name "MPN") "ERJ-2RKF5621X"))
      (libsource (lib "eagle-import") (part "R-US_0402-B-NOSILK"))
    )
    (comp (ref "U8")
      (value "QPC1022")
      (footprint "eagle-import:QPC1022")
      (fields (field (name "MFR") "Qorvo"))
      (libsource (lib "eagle-import") (part "QPC1022"))
    )
    (comp (ref "C6")
      (value "100n")
      (footprint "eagle-import:.0402-B-NOSILK")
      (fields (field (name "MFR") "TDK") (field (name "MPN") "CGA2B1X7R1C104K050BC"))
      (libsource (lib "eagle-import") (part "C-EU0402-B-NOSILK"))
    )
    (comp (ref "C8")
      (value "100n")
      (footprint "eagle-import:.0402-B-NOSILK")
      (fields (field (name "MFR") "TDK") (field (name "MPN") "CGA2B1X7R1C104K050BC"))
      (libsource (lib "eagle-import") (part "C-EU0402-B-NOSILK"))
    )
    (comp (ref "C39")
      (value "100n")
      (footprint "eagle-import:.0402-B-NOSILK")
      (fields (field (name "MFR") "TDK") (field (name "MPN") "CGA2B1X7R1C104K050BC"))
      (libsource (lib "eagle-import") (part "C-EU0402-B-NOSILK"))
    )
    (comp (ref "C41")
      (value "100n")
      (footprint "eagle-import:.0402-B-NOSILK")
      (fields (field (name "MFR") "TDK") (field (name "MPN") "CGA2B1X7R1C104K050BC"))
      (libsource (lib "eagle-import") (part "C-EU0402-B-NOSILK"))
    )
    (comp (ref "H1")
      (value "STAND-OFFTIGHT")
      (footprint "eagle-import:STAND-OFF-TIGHT")
      (libsource (lib "eagle-import") (part "STAND-OFFTIGHT"))
    )
    (comp (ref "H2")
      (value "STAND-OFFTIGHT")
      (footprint "eagle-import:STAND-OFF-TIGHT")
      (libsource (lib "eagle-import") (part "STAND-OFFTIGHT"))
    )
    (comp (ref "H3")
      (value "STAND-OFFTIGHT")
      (footprint "eagle-import:STAND-OFF-TIGHT")
      (libsource (lib "eagle-import") (part "STAND-OFFTIGHT"))
    )
    (comp (ref "H4")
      (value "STAND-OFFTIGHT")
      (footprint "eagle-import:STAND-OFF-TIGHT")
      (libsource (lib "eagle-import") (part "STAND-OFFTIGHT"))
    )
    (comp (ref "JP1")
      (value "PINHD-1X3")
      (footprint "eagle-import:1X03")
      (fields (field (name "MFR") "Molex") (field (name "MPN") "22-23-2031"))
      (libsource (lib "eagle-import") (part "PINHD-1X3"))
    )
    (comp (ref "LED1")
      (value "LTST-C193KRKT-5A")
      (footprint "eagle-import:LEDC1607X80N")
      (fields (field (name "MFR") "Lite-On"))
      (libsource (lib "eagle-import") (part "LTST-C193KRKT-5A"))
    )
    (comp (ref "LED2")
      (value "LTST-C193KGKT-5A")
      (footprint "eagle-import:LEDC1607X80N")
      (fields (field (name "MFR") "Lite-On"))
      (libsource (lib "eagle-import") (part "LTST-C193KGKT-5A"))
    )
    (comp (ref "R5")
      (value "10k")
      (footprint "eagle-import:.0402-B-NOSILK")
      (fields (field (name "MFR") "Panasonic") (field (name "MPN") "ERJ-2GEJ103X"))
      (libsource (lib "eagle-import") (part "R-US_0402-B-NOSILK"))
    )
    (comp (ref "R11")
      (value "499k")
      (footprint "eagle-import:.0402-B-NOSILK")
      (fields (field (name "MFR") "Panasonic") (field (name "MPN") "ERJ-2RKF4993X"))
      (libsource (lib "eagle-import") (part "R-US_0402-B-NOSILK"))
    )
    (comp (ref "R12")
      (value "499k")
      (footprint "eagle-import:.0402-B-NOSILK")
      (fields (field (name "MFR") "Panasonic") (field (name "MPN") "ERJ-2RKF4993X"))
      (libsource (lib "eagle-import") (part "R-US_0402-B-NOSILK"))
    )
    (comp (ref "R32")
      (value "1k")
      (footprint "eagle-import:.0402-B-NOSILK")
      (fields (field (name "MFR") "Panasonic") (field (name "MPN") "ERJ-2GEJ102X"))
      (libsource (lib "eagle-import") (part "R-US_0402-B-NOSILK"))
    )
    (comp (ref "R36")
      (value "1k")
      (footprint "eagle-import:.0402-B-NOSILK")
      (fields (field (name "MFR") "Panasonic") (field (name "MPN") "ERJ-2GEJ102X"))
      (libsource (lib "eagle-import") (part "R-US_0402-B-NOSILK"))
    )
    (comp (ref "R37")
      (value "10k")
      (footprint "eagle-import:.0402-B-NOSILK")
      (fields (field (name "MFR") "Panasonic") (field (name "MPN") "ERJ-2GEJ103X"))
      (libsource (lib "eagle-import") (part "R-US_0402-B-NOSILK"))
    )
    (comp (ref "SW1")
      (value "TL36PO")
      (footprint "eagle-import:TL3XPO")
      (fields (field (name "MFR") "APEM Inc.") (field (name "MPN") "TL36P005000"))
      (libsource (lib "eagle-import") (part "TL36PO"))
    )
    (comp (ref "U1")
      (value "SN74LVC1G32DBVR")
      (footprint "eagle-import:DBV5")
      (fields (field (name "MFR") "Texas Instruments"))
      (libsource (lib "eagle-import") (part "SN74LVC1G32DBVR"))
    )
    (comp (ref "U2")
      (value "LTC6994-1")
      (footprint "eagle-import:TSOT-23_S6")
      (fields (field (name "MFR") "Linear Technology"))
      (libsource (lib "eagle-import") (part "LTC6994CS6-1PBF"))
    )
    (comp (ref "U3")
      (value "LTC6994-1")
      (footprint "eagle-import:TSOT-23_S6")
      (fields (field (name "MFR") "Linear Technology"))
      (libsource (lib "eagle-import") (part "LTC6994CS6-1PBF"))
    )
    (comp (ref "U11")
      (value "SN74LV1T34DBVR")
      (footprint "eagle-import:SOT95P280X145-5N")
      (fields (field (name "MFR") "Texas Instruments"))
      (libsource (lib "eagle-import") (part "SN74LV1T34DBVR"))
    )
    (comp (ref "C15")
      (value "100nF")
      (footprint "eagle-import:.0402-B-NOSILK")
      (fields (field (name "MFR") "TDK") (field (name "MPN") "CGA2B1X7R1C104K050BC"))
      (libsource (lib "eagle-import") (part "C-EU0402-B-NOSILK"))
    )
    (comp (ref "C16")
      (value "100nF")
      (footprint "eagle-import:.0402-B-NOSILK")
      (fields (field (name "MFR") "TDK") (field (name "MPN") "CGA2B1X7R1C104K050BC"))
      (libsource (lib "eagle-import") (part "C-EU0402-B-NOSILK"))
    )
    (comp (ref "C17")
      (value "100nF")
      (footprint "eagle-import:.0402-B-NOSILK")
      (fields (field (name "MFR") "TDK") (field (name "MPN") "CGA2B1X7R1C104K050BC"))
      (libsource (lib "eagle-import") (part "C-EU0402-B-NOSILK"))
    )
    (comp (ref "C18")
      (value "100pF")
      (footprint "eagle-import:.0402-B-NOSILK")
      (fields (field (name "MFR") "Murata") (field (name "MPN") "GCM1555C1H101JA16D"))
      (libsource (lib "eagle-import") (part "C-EU0402-B-NOSILK"))
    )
    (comp (ref "C19")
      (value "1000pF")
      (footprint "eagle-import:.0402-B-NOSILK")
      (fields (field (name "MFR") "TDK") (field (name "MPN") "CGA2B2NP01H102J050BA"))
      (libsource (lib "eagle-import") (part "C-EU0402-B-NOSILK"))
    )
    (comp (ref "C20")
      (value "100pF")
      (footprint "eagle-import:.0603-C-NOSILK")
      (fields (field (name "MFR") "Murata") (field (name "MPN") "GCM1885C1H101JA16D "))
      (libsource (lib "eagle-import") (part "C-EU0603-C-NOSILK"))
    )
    (comp (ref "C21")
      (value "3.0pF")
      (footprint "eagle-import:.0402-C-NOSILK")
      (fields (field (name "MFR") "Taiyo Yuden") (field (name "MPN") "UVK105CG030JW-F"))
      (libsource (lib "eagle-import") (part "C-EU0402-C-NOSILK"))
    )
    (comp (ref "C22")
      (value "2.2pF")
      (footprint "eagle-import:.0402-C-NOSILK")
      (fields (field (name "MFR") "Taiyo Yuden") (field (name "MPN") "UVK105CG2R2JW-F"))
      (libsource (lib "eagle-import") (part "C-EU0402-C-NOSILK"))
    )
    (comp (ref "C23")
      (value "1.6pF")
      (footprint "eagle-import:.0402-C-NOSILK")
      (fields (field (name "MFR") "Murata") (field (name "MPN") "GJM1555C1H1R6BB01D"))
      (libsource (lib "eagle-import") (part "C-EU0402-C-NOSILK"))
    )
    (comp (ref "C24")
      (value "4.7pF")
      (footprint "eagle-import:.0603-C-NOSILK")
      (fields (field (name "MFR") "AVX Corp.") (field (name "MPN") "06032U4R7BAT2A "))
      (libsource (lib "eagle-import") (part "C-EU0603-C-NOSILK"))
    )
    (comp (ref "J1")
      (value "142-0701-851_ALT")
      (footprint "eagle-import:142-0701-851")
      (fields (field (name "MFR") "Cinch") (field (name "MPN") "142-0701-851"))
      (libsource (lib "eagle-import") (part "142-0701-851_ALT"))
    )
    (comp (ref "L1")
      (value "1008HQ-10NXJLB1008_IMPERIAL_2520_METRIC")
      (footprint "eagle-import:INDC2520X120N")
      (fields (field (name "MFR") "COILCRAFT") (field (name "MPN") "1008HQ-10NXJLB"))
      (libsource (lib "eagle-import") (part "1008HQ-10NXJLB1008_IMPERIAL_2520_METRIC"))
    )
    (comp (ref "L2")
      (value "6.8nH")
      (footprint "eagle-import:0805CS")
      (fields (field (name "MFR") "COILCRAFT") (field (name "MPN") "0805CS-060XJLC"))
      (libsource (lib "eagle-import") (part "0805CS-060XJLC"))
    )
    (comp (ref "L3")
      (value "1.2nH")
      (footprint "eagle-import:0402CS1N2XJLW")
      (fields (field (name "MFR") "COILCRAFT") (field (name "MPN") "0402CS-1N2XJLW"))
      (libsource (lib "eagle-import") (part "0402CS-1N2XJLW"))
    )
    (comp (ref "R1")
      (value "147")
      (footprint "eagle-import:.0603-C-NOSILK")
      (fields (field (name "MFR") "Panasonic") (field (name "MPN") "ERJ-3EKF1470V"))
      (libsource (lib "eagle-import") (part "R-US_0603-C-NOSILK"))
    )
    (comp (ref "R2")
      (value "147")
      (footprint "eagle-import:.0603-C-NOSILK")
      (fields (field (name "MFR") "Panasonic") (field (name "MPN") "ERJ-3EKF1470V"))
      (libsource (lib "eagle-import") (part "R-US_0603-C-NOSILK"))
    )
    (comp (ref "R3")
      (value "17.8")
      (footprint "eagle-import:.0603-C-NOSILK")
      (fields (field (name "MFR") "Panasonic") (field (name "MPN") "ERJ-3EKF17R8V"))
      (libsource (lib "eagle-import") (part "R-US_0603-C-NOSILK"))
    )
    (comp (ref "R4")
      (value "294")
      (footprint "eagle-import:.0603-C-NOSILK")
      (fields (field (name "MFR") "Panasonic") (field (name "MPN") "ERJ-3EKF2940V"))
      (libsource (lib "eagle-import") (part "R-US_0603-C-NOSILK"))
    )
    (comp (ref "R17")
      (value "0")
      (footprint "eagle-import:R0805")
      (fields (field (name "MFR") "Panasonic") (field (name "MPN") "ERJ-6GEY0R00V"))
      (libsource (lib "eagle-import") (part "rcl_334_R-US_R0805"))
    )
    (comp (ref "R18")
      (value "1.2")
      (footprint "eagle-import:R0402")
      (fields (field (name "MFR") "Panasonic") (field (name "MPN") "ERJ-2GEJ1R2X"))
      (libsource (lib "eagle-import") (part "rcl_334_R-US_R0402"))
    )
    (comp (ref "R19")
      (value "110")
      (footprint "eagle-import:.0402-B-NOSILK")
      (fields (field (name "MFR") "Panasonic") (field (name "MPN") "ERJ-2RKF1100X"))
      (libsource (lib "eagle-import") (part "R-US_0402-B-NOSILK"))
    )
    (comp (ref "R20")
      (value "220")
      (footprint "eagle-import:.0603-C-NOSILK")
      (fields (field (name "MFR") "Panasonic") (field (name "MPN") "ERJ-3EKF2200V"))
      (libsource (lib "eagle-import") (part "R-US_0603-C-NOSILK"))
    )
    (comp (ref "U10")
      (value "TQP9111")
      (footprint "eagle-import:QFN50P400X400X102-21N")
      (fields (field (name "MFR") "Qorvo"))
      (libsource (lib "eagle-import") (part "TQP9111"))
    )
  )
  (nets
    (net (code "1") (name "+5V") (class "Default")
      (node (ref "C10") (pin "1") (pinfunction "1_1") (pintype "passive"))
      (node (ref "C14") (pin "1") (pinfunction "1_1") (pintype "passive"))
      (node (ref "C30") (pin "1") (pinfunction "1_1") (pintype "passive"))
      (node (ref "C31") (pin "1") (pinfunction "1_1") (pintype "passive"))
      (node (ref "C34") (pin "1") (pinfunction "1_1") (pintype "passive"))
      (node (ref "C35") (pin "1") (pinfunction "1_1") (pintype "passive"))
      (node (ref "C39") (pin "1") (pinfunction "1_1") (pintype "passive"))
      (node (ref "C41") (pin "1") (pinfunction "1_1") (pintype "passive"))
      (node (ref "C5") (pin "1") (pinfunction "1_1") (pintype "passive"))
      (node (ref "C6") (pin "1") (pinfunction "1_1") (pintype "passive"))
      (node (ref "C7") (pin "1") (pinfunction "1_1") (pintype "passive"))
      (node (ref "C8") (pin "1") (pinfunction "1_1") (pintype "passive"))
      (node (ref "C9") (pin "1") (pinfunction "1_1") (pintype "passive"))
      (node (ref "JP6") (pin "1") (pinfunction "1_1") (pintype "passive"))
      (node (ref "JP6") (pin "2") (pinfunction "2_2") (pintype "passive"))
      (node (ref "LED2") (pin "2") (pinfunction "A_2") (pintype "bidirectional"))
      (node (ref "R14") (pin "2") (pinfunction "2_2") (pintype "passive"))
      (node (ref "R15") (pin "1") (pinfunction "1_1") (pintype "passive"))
      (node (ref "R17") (pin "2") (pinfunction "2_2") (pintype "passive"))
      (node (ref "R23") (pin "2") (pinfunction "2_2") (pintype "passive"))
      (node (ref "R24") (pin "1") (pinfunction "1_1") (pintype "passive"))
      (node (ref "R5") (pin "2") (pinfunction "2_2") (pintype "passive"))
      (node (ref "U1") (pin "5") (pinfunction "VCC_5") (pintype "power_in"))
      (node (ref "U11") (pin "5") (pinfunction "VCC_5") (pintype "bidirectional"))
      (node (ref "U12") (pin "5") (pinfunction "VCC_5") (pintype "power_in"))
      (node (ref "U2") (pin "5") (pinfunction "V+_5") (pintype "power_in"))
      (node (ref "U3") (pin "4") (pinfunction "DIV_4") (pintype "input"))
      (node (ref "U3") (pin "5") (pinfunction "V+_5") (pintype "power_in"))
      (node (ref "U6") (pin "5") (pinfunction "VCC_5") (pintype "bidirectional"))
      (node (ref "U7") (pin "7") (pinfunction "VDD_7") (pintype "power_in"))
      (node (ref "U8") (pin "7") (pinfunction "VDD_7") (pintype "power_in"))
      (node (ref "U9") (pin "5") (pinfunction "VCC_5") (pintype "bidirectional"))
    )
    (net (code "2") (name "ANT_SEL+3.3V") (class "Default")
      (node (ref "JP3") (pin "1") (pinfunction "1_1") (pintype "passive"))
      (node (ref "JP3") (pin "3") (pinfunction "3_3") (pintype "passive"))
      (node (ref "R28") (pin "2") (pinfunction "2_2") (pintype "passive"))
      (node (ref "U9") (pin "2") (pinfunction "A_2") (pintype "bidirectional"))
    )
    (net (code "3") (name "ANT_SEL_+5.0V") (class "Default")
      (node (ref "R21") (pin "1") (pinfunction "1_1") (pintype "passive"))
      (node (ref "U9") (pin "4") (pinfunction "Y_4") (pintype "bidirectional"))
    )
    (net (code "4") (name "AR9271_TX_+3.3V") (class "Default")
      (node (ref "JP1") (pin "1") (pinfunction "1_1") (pintype "passive"))
      (node (ref "JP1") (pin "3") (pinfunction "3_3") (pintype "passive"))
      (node (ref "R37") (pin "2") (pinfunction "2_2") (pintype "passive"))
      (node (ref "U11") (pin "2") (pinfunction "A_2") (pintype "bidirectional"))
    )
    (net (code "5") (name "GND") (class "Default")
      (node (ref "C10") (pin "2") (pinfunction "2_2") (pintype "passive"))
      (node (ref "C11") (pin "2") (pinfunction "2_2") (pintype "passive"))
      (node (ref "C12") (pin "2") (pinfunction "2_2") (pintype "passive"))
      (node (ref "C14") (pin "2") (pinfunction "2_2") (pintype "passive"))
      (node (ref "C15") (pin "2") (pinfunction "2_2") (pintype "passive"))
      (node (ref "C16") (pin "2") (pinfunction "2_2") (pintype "passive"))
      (node (ref "C17") (pin "2") (pinfunction "2_2") (pintype "passive"))
      (node (ref "C18") (pin "2") (pinfunction "2_2") (pintype "passive"))
      (node (ref "C19") (pin "2") (pinfunction "2_2") (pintype "passive"))
      (node (ref "C2") (pin "1") (pinfunction "1_1") (pintype "passive"))
      (node (ref "C21") (pin "2") (pinfunction "2_2") (pintype "passive"))
      (node (ref "C22") (pin "2") (pinfunction "2_2") (pintype "passive"))
      (node (ref "C23") (pin "2") (pinfunction "2_2") (pintype "passive"))
      (node (ref "C27") (pin "1") (pinfunction "1_1") (pintype "passive"))
      (node (ref "C29") (pin "2") (pinfunction "2_2") (pintype "passive"))
      (node (ref "C30") (pin "2") (pinfunction "2_2") (pintype "passive"))
      (node (ref "C31") (pin "2") (pinfunction "2_2") (pintype "passive"))
      (node (ref "C32") (pin "2") (pinfunction "2_2") (pintype "passive"))
      (node (ref "C33") (pin "2") (pinfunction "2_2") (pintype "passive"))
      (node (ref "C34") (pin "2") (pinfunction "2_2") (pintype "passive"))
      (node (ref "C35") (pin "2") (pinfunction "2_2") (pintype "passive"))
      (node (ref "C39") (pin "2") (pinfunction "2_2") (pintype "passive"))
      (node (ref "C4") (pin "2") (pinfunction "2_2") (pintype "passive"))
      (node (ref "C41") (pin "2") (pinfunction "2_2") (pintype "passive"))
      (node (ref "C5") (pin "2") (pinfunction "2_2") (pintype "passive"))
      (node (ref "C6") (pin "2") (pinfunction "2_2") (pintype "passive"))
      (node (ref "C7") (pin "2") (pinfunction "2_2") (pintype "passive"))
      (node (ref "C8") (pin "2") (pinfunction "2_2") (pintype "passive"))
      (node (ref "C9") (pin "2") (pinfunction "2_2") (pintype "passive"))
      (node (ref "FL1") (pin "2") (pinfunction "GND_2") (pintype "power_in"))
      (node (ref "FL1") (pin "3") (pinfunction "GND_3") (pintype "power_in"))
      (node (ref "FL1") (pin "5") (pinfunction "GND_5") (pintype "power_in"))
      (node (ref "FL2") (pin "2") (pinfunction "GND_2") (pintype "power_in"))
      (node (ref "FL2") (pin "3") (pinfunction "GND_3") (pintype "power_in"))
      (node (ref "FL2") (pin "5") (pinfunction "GND_5") (pintype "power_in"))
      (node (ref "J1") (pin "GND1") (pinfunction "GND_GND1") (pintype "bidirectional"))
      (node (ref "J1") (pin "GND2") (pinfunction "GND_GND2") (pintype "bidirectional"))
      (node (ref "J1") (pin "GND3") (pinfunction "GND_GND3") (pintype "bidirectional"))
      (node (ref "J1") (pin "GND4") (pinfunction "GND_GND4") (pintype "bidirectional"))
      (node (ref "J2") (pin "GND1") (pinfunction "GND_GND1") (pintype "bidirectional"))
      (node (ref "J2") (pin "GND2") (pinfunction "GND_GND2") (pintype "bidirectional"))
      (node (ref "J2") (pin "GND3") (pinfunction "GND_GND3") (pintype "bidirectional"))
      (node (ref "J2") (pin "GND4") (pinfunction "GND_GND4") (pintype "bidirectional"))
      (node (ref "J3") (pin "GND1") (pinfunction "GND_GND1") (pintype "bidirectional"))
      (node (ref "J3") (pin "GND2") (pinfunction "GND_GND2") (pintype "bidirectional"))
      (node (ref "J3") (pin "GND3") (pinfunction "GND_GND3") (pintype "bidirectional"))
      (node (ref "J3") (pin "GND4") (pinfunction "GND_GND4") (pintype "bidirectional"))
      (node (ref "J4") (pin "GND1") (pinfunction "GND_GND1") (pintype "bidirectional"))
      (node (ref "J4") (pin "GND2") (pinfunction "GND_GND2") (pintype "bidirectional"))
      (node (ref "J4") (pin "GND3") (pinfunction "GND_GND3") (pintype "bidirectional"))
      (node (ref "J4") (pin "GND4") (pinfunction "GND_GND4") (pintype "bidirectional"))
      (node (ref "J6") (pin "GND1") (pinfunction "GND_GND1") (pintype "bidirectional"))
      (node (ref "J6") (pin "GND2") (pinfunction "GND_GND2") (pintype "bidirectional"))
      (node (ref "J6") (pin "GND3") (pinfunction "GND_GND3") (pintype "bidirectional"))
      (node (ref "J6") (pin "GND4") (pinfunction "GND_GND4") (pintype "bidirectional"))
      (node (ref "J7") (pin "GND1") (pinfunction "GND_GND1") (pintype "bidirectional"))
      (node (ref "J7") (pin "GND2") (pinfunction "GND_GND2") (pintype "bidirectional"))
      (node (ref "J7") (pin "GND3") (pinfunction "GND_GND3") (pintype "bidirectional"))
      (node (ref "J7") (pin "GND4") (pinfunction "GND_GND4") (pintype "bidirectional"))
      (node (ref "JP1") (pin "2") (pinfunction "2_2") (pintype "passive"))
      (node (ref "JP3") (pin "2") (pinfunction "2_2") (pintype "passive"))
      (node (ref "JP4") (pin "2") (pinfunction "2_2") (pintype "passive"))
      (node (ref "JP6") (pin "3") (pinfunction "3_3") (pintype "passive"))
      (node (ref "JP6") (pin "4") (pinfunction "4_4") (pintype "passive"))
      (node (ref "R10") (pin "2") (pinfunction "2_2") (pintype "passive"))
      (node (ref "R11") (pin "1") (pinfunction "1_1") (pintype "passive"))
      (node (ref "R12") (pin "1") (pinfunction "1_1") (pintype "passive"))
      (node (ref "R13") (pin "2") (pinfunction "2_2") (pintype "passive"))
      (node (ref "R16") (pin "2") (pinfunction "2_2") (pintype "passive"))
      (node (ref "R2") (pin "1") (pinfunction "1_1") (pintype "passive"))
      (node (ref "R22") (pin "2") (pinfunction "2_2") (pintype "passive"))
      (node (ref "R25") (pin "2") (pinfunction "2_2") (pintype "passive"))
      (node (ref "R27") (pin "2") (pinfunction "2_2") (pintype "passive"))
      (node (ref "R28") (pin "1") (pinfunction "1_1") (pintype "passive"))
      (node (ref "R29") (pin "1") (pinfunction "1_1") (pintype "passive"))
      (node (ref "R31") (pin "2") (pinfunction "2_2") (pintype "passive"))
      (node (ref "R32") (pin "1") (pinfunction "1_1") (pintype "passive"))
      (node (ref "R36") (pin "1") (pinfunction "1_1") (pintype "passive"))
      (node (ref "R37") (pin "1") (pinfunction "1_1") (pintype "passive"))
      (node (ref "R4") (pin "2") (pinfunction "2_2") (pintype "passive"))
      (node (ref "R7") (pin "2") (pinfunction "2_2") (pintype "passive"))
      (node (ref "R8") (pin "2") (pinfunction "2_2") (pintype "passive"))
      (node (ref "SW1") (pin "1") (pinfunction "O_1") (pintype "passive"))
      (node (ref "U1") (pin "3") (pinfunction "GND_3") (pintype "power_in"))
      (node (ref "U10") (pin "1") (pinfunction "GND_1") (pintype "power_in"))
      (node (ref "U10") (pin "10") (pinfunction "GND_10") (pintype "power_in"))
      (node (ref "U10") (pin "11") (pinfunction "GND_11") (pintype "power_in"))
      (node (ref "U10") (pin "15") (pinfunction "GND_15") (pintype "power_in"))
      (node (ref "U10") (pin "17") (pinfunction "GND_17") (pintype "power_in"))
      (node (ref "U10") (pin "19") (pinfunction "GND_19") (pintype "power_in"))
      (node (ref "U10") (pin "21") (pinfunction "GND_21") (pintype "power_in"))
      (node (ref "U10") (pin "5") (pinfunction "GND_5") (pintype "power_in"))
      (node (ref "U10") (pin "7") (pinfunction "GND_7") (pintype "power_in"))
      (node (ref "U10") (pin "9") (pinfunction "GND_9") (pintype "power_in"))
      (node (ref "U11") (pin "3") (pinfunction "GND_3") (pintype "bidirectional"))
      (node (ref "U12") (pin "3") (pinfunction "GND_3") (pintype "power_in"))
      (node (ref "U2") (pin "2") (pinfunction "GND_2") (pintype "power_in"))
      (node (ref "U2") (pin "4") (pinfunction "DIV_4") (pintype "input"))
      (node (ref "U3") (pin "2") (pinfunction "GND_2") (pintype "power_in"))
      (node (ref "U4") (pin "1") (pinfunction "GND_1") (pintype "power_in"))
      (node (ref "U4") (pin "3") (pinfunction "GND_3") (pintype "power_in"))
      (node (ref "U4") (pin "4") (pinfunction "GND_4") (pintype "power_in"))
      (node (ref "U4") (pin "5") (pinfunction "GND_5") (pintype "power_in"))
      (node (ref "U4") (pin "8") (pinfunction "GND_8") (pintype "power_in"))
      (node (ref "U4") (pin "PAD") (pinfunction "GND_PAD") (pintype "power_in"))
      (node (ref "U5") (pin "1") (pinfunction "GND_1") (pintype "power_in"))
      (node (ref "U5") (pin "3") (pinfunction "GND_3") (pintype "power_in"))
      (node (ref "U5") (pin "4") (pinfunction "GND_4") (pintype "power_in"))
      (node (ref "U5") (pin "5") (pinfunction "GND_5") (pintype "power_in"))
      (node (ref "U5") (pin "8") (pinfunction "GND_8") (pintype "power_in"))
      (node (ref "U5") (pin "PAD") (pinfunction "GND_PAD") (pintype "power_in"))
      (node (ref "U6") (pin "3") (pinfunction "GND_3") (pintype "bidirectional"))
      (node (ref "U7") (pin "1") (pinfunction "GND_1") (pintype "power_in"))
      (node (ref "U7") (pin "3") (pinfunction "GND_3") (pintype "power_in"))
      (node (ref "U7") (pin "9") (pinfunction "GND_9") (pintype "power_in"))
      (node (ref "U8") (pin "1") (pinfunction "GND_1") (pintype "power_in"))
      (node (ref "U8") (pin "3") (pinfunction "GND_3") (pintype "power_in"))
      (node (ref "U8") (pin "9") (pinfunction "GND_9") (pintype "power_in"))
      (node (ref "U9") (pin "3") (pinfunction "GND_3") (pintype "bidirectional"))
    )
    (net (code "6") (name "LNA_DISABLE+3.3V") (class "Default")
      (node (ref "JP4") (pin "1") (pinfunction "1_1") (pintype "passive"))
      (node (ref "JP4") (pin "3") (pinfunction "3_3") (pintype "passive"))
      (node (ref "R29") (pin "2") (pinfunction "2_2") (pintype "passive"))
      (node (ref "U6") (pin "2") (pinfunction "A_2") (pintype "bidirectional"))
    )
    (net (code "7") (name "LNA_DISABLE_+5.0V") (class "Default")
      (node (ref "U12") (pin "2") (pinfunction "B_2") (pintype "input"))
      (node (ref "U6") (pin "4") (pinfunction "Y_4") (pintype "bidirectional"))
    )
    (net (code "8") (name "N$17") (class "Default")
      (node (ref "R30") (pin "2") (pinfunction "2_2") (pintype "passive"))
      (node (ref "U12") (pin "4") (pinfunction "Y_4") (pintype "output"))
    )
    (net (code "9") (name "Net-(C1-Pad1)") (class "Default")
      (node (ref "C1") (pin "1") (pinfunction "1_1") (pintype "passive"))
      (node (ref "R10") (pin "1") (pinfunction "1_1") (pintype "passive"))
      (node (ref "R9") (pin "2") (pinfunction "2_2") (pintype "passive"))
    )
    (net (code "10") (name "Net-(C2-Pad2)") (class "Default")
      (node (ref "C2") (pin "2") (pinfunction "2_2") (pintype "passive"))
      (node (ref "C4") (pin "1") (pinfunction "1_1") (pintype "passive"))
      (node (ref "L5") (pin "2") (pinfunction "2_2") (pintype "bidirectional"))
      (node (ref "R14") (pin "1") (pinfunction "1_1") (pintype "passive"))
    )
    (net (code "11") (name "Net-(C15-Pad1)") (class "Default")
      (node (ref "C15") (pin "1") (pinfunction "1_1") (pintype "passive"))
      (node (ref "C16") (pin "1") (pinfunction "1_1") (pintype "passive"))
      (node (ref "C17") (pin "1") (pinfunction "1_1") (pintype "passive"))
      (node (ref "C19") (pin "1") (pinfunction "1_1") (pintype "passive"))
      (node (ref "L1") (pin "2") (pinfunction "2_2") (pintype "bidirectional"))
      (node (ref "L2") (pin "2") (pinfunction "2_2") (pintype "bidirectional"))
      (node (ref "R17") (pin "1") (pinfunction "1_1") (pintype "passive"))
      (node (ref "R20") (pin "2") (pinfunction "2_2") (pintype "passive"))
    )
    (net (code "12") (name "Net-(C20-Pad1)") (class "Default")
      (node (ref "C20") (pin "1") (pinfunction "1_1") (pintype "passive"))
      (node (ref "C23") (pin "1") (pinfunction "1_1") (pintype "passive"))
      (node (ref "L3") (pin "2") (pinfunction "2_2") (pintype "bidirectional"))
    )
    (net (code "13") (name "Net-(C21-Pad1)") (class "Default")
      (node (ref "C21") (pin "1") (pinfunction "1_1") (pintype "passive"))
      (node (ref "L3") (pin "1") (pinfunction "1_1") (pintype "bidirectional"))
      (node (ref "U10") (pin "12") (pinfunction "RFOUT_12") (pintype "output"))
      (node (ref "U10") (pin "13") (pinfunction "RFOUT_13") (pintype "output"))
      (node (ref "U10") (pin "14") (pinfunction "RFOUT_14") (pintype "output"))
    )
    (net (code "14") (name "Net-(C22-Pad1)") (class "Default")
      (node (ref "C22") (pin "1") (pinfunction "1_1") (pintype "passive"))
      (node (ref "C24") (pin "2") (pinfunction "2_2") (pintype "passive"))
      (node (ref "R18") (pin "1") (pinfunction "1_1") (pintype "passive"))
    )
    (net (code "15") (name "Net-(C24-Pad1)") (class "Default")
      (node (ref "C24") (pin "1") (pinfunction "1_1") (pintype "passive"))
      (node (ref "R3") (pin "2") (pinfunction "2_2") (pintype "passive"))
      (node (ref "R4") (pin "1") (pinfunction "1_1") (pintype "passive"))
    )
    (net (code "16") (name "Net-(C27-Pad2)") (class "Default")
      (node (ref "C27") (pin "2") (pinfunction "2_2") (pintype "passive"))
      (node (ref "C29") (pin "1") (pinfunction "1_1") (pintype "passive"))
      (node (ref "L4") (pin "2") (pinfunction "2_2") (pintype "bidirectional"))
      (node (ref "R23") (pin "1") (pinfunction "1_1") (pintype "passive"))
    )
    (net (code "17") (name "Net-(C28-Pad2)") (class "Default")
      (node (ref "C28") (pin "2") (pinfunction "2_2") (pintype "passive"))
      (node (ref "R6") (pin "1") (pinfunction "1_1") (pintype "passive"))
      (node (ref "R8") (pin "1") (pinfunction "1_1") (pintype "passive"))
    )
    (net (code "18") (name "Net-(FL1-OUT)") (class "Default")
      (node (ref "C26") (pin "1") (pinfunction "1_1") (pintype "passive"))
      (node (ref "FL1") (pin "4") (pinfunction "OUT_4") (pintype "passive"))
    )
    (net (code "19") (name "Net-(FL2-IN)") (class "Default")
      (node (ref "FL2") (pin "1") (pinfunction "IN_1") (pintype "passive"))
      (node (ref "R6") (pin "2") (pinfunction "2_2") (pintype "passive"))
      (node (ref "R7") (pin "1") (pinfunction "1_1") (pintype "passive"))
    )
    (net (code "20") (name "Net-(FL2-OUT)") (class "Default")
      (node (ref "FL2") (pin "4") (pinfunction "OUT_4") (pintype "passive"))
      (node (ref "R13") (pin "1") (pinfunction "1_1") (pintype "passive"))
      (node (ref "R9") (pin "1") (pinfunction "1_1") (pintype "passive"))
    )
    (net (code "21") (name "Net-(J1-CTR)") (class "Default")
      (node (ref "J1") (pin "RF1") (pinfunction "CTR_RF1") (pintype "bidirectional"))
      (node (ref "R1") (pin "2") (pinfunction "2_2") (pintype "passive"))
      (node (ref "R3") (pin "1") (pinfunction "1_1") (pintype "passive"))
    )
    (net (code "22") (name "Net-(J2-CTR)") (class "Default")
      (node (ref "J2") (pin "RF1") (pinfunction "CTR_RF1") (pintype "bidirectional"))
      (node (ref "U7") (pin "8") (pinfunction "RF2_8") (pintype "bidirectional"))
    )
    (net (code "23") (name "Net-(J3-CTR)") (class "Default")
      (node (ref "J3") (pin "RF1") (pinfunction "CTR_RF1") (pintype "bidirectional"))
      (node (ref "U7") (pin "4") (pinfunction "RF1_4") (pintype "bidirectional"))
    )
    (net (code "24") (name "Net-(J4-CTR)") (class "Default")
      (node (ref "C3") (pin "2") (pinfunction "2_2") (pintype "passive"))
      (node (ref "J4") (pin "RF1") (pinfunction "CTR_RF1") (pintype "bidirectional"))
    )
    (net (code "25") (name "Net-(J6-CTR)") (class "Default")
      (node (ref "J6") (pin "RF1") (pinfunction "CTR_RF1") (pintype "bidirectional"))
      (node (ref "J7") (pin "RF1") (pinfunction "CTR_RF1") (pintype "bidirectional"))
    )
    (net (code "26") (name "Net-(LED1-A)") (class "Default")
      (node (ref "LED1") (pin "2") (pinfunction "A_2") (pintype "bidirectional"))
      (node (ref "U1") (pin "4") (pinfunction "Y_4") (pintype "output"))
      (node (ref "U2") (pin "1") (pinfunction "IN_1") (pintype "input"))
      (node (ref "U3") (pin "1") (pinfunction "IN_1") (pintype "input"))
    )
    (net (code "27") (name "Net-(LED1-K)") (class "Default")
      (node (ref "LED1") (pin "1") (pinfunction "K_1") (pintype "bidirectional"))
      (node (ref "R32") (pin "2") (pinfunction "2_2") (pintype "passive"))
    )
    (net (code "28") (name "Net-(LED2-K)") (class "Default")
      (node (ref "LED2") (pin "1") (pinfunction "K_1") (pintype "bidirectional"))
      (node (ref "R36") (pin "2") (pinfunction "2_2") (pintype "passive"))
    )
    (net (code "29") (name "Net-(R1-Pad1)") (class "Default")
      (node (ref "R1") (pin "1") (pinfunction "1_1") (pintype "passive"))
      (node (ref "R2") (pin "2") (pinfunction "2_2") (pintype "passive"))
    )
    (net (code "30") (name "Net-(R18-Pad2)") (class "Default")
      (node (ref "R18") (pin "2") (pinfunction "2_2") (pintype "passive"))
      (node (ref "U10") (pin "2") (pinfunction "RFIN_2") (pintype "input"))
      (node (ref "U10") (pin "3") (pinfunction "RFIN_3") (pintype "input"))
      (node (ref "U10") (pin "4") (pinfunction "RFIN_4") (pintype "input"))
    )
    (net (code "31") (name "Net-(SW1-P)") (class "Default")
      (node (ref "SW1") (pin "2") (pinfunction "P_2") (pintype "passive"))
      (node (ref "U1") (pin "1") (pinfunction "A_1") (pintype "input"))
    )
    (net (code "32") (name "Net-(SW1-S)") (class "Default")
      (node (ref "R5") (pin "1") (pinfunction "1_1") (pintype "passive"))
      (node (ref "SW1") (pin "3") (pinfunction "S_3") (pintype "passive"))
    )
    (net (code "33") (name "Net-(U1-B)") (class "Default")
      (node (ref "U1") (pin "2") (pinfunction "B_2") (pintype "input"))
      (node (ref "U11") (pin "4") (pinfunction "Y_4") (pintype "bidirectional"))
    )
    (net (code "34") (name "Net-(U2-SET)") (class "Default")
      (node (ref "R11") (pin "2") (pinfunction "2_2") (pintype "passive"))
      (node (ref "U2") (pin "3") (pinfunction "SET_3") (pintype "input"))
    )
    (net (code "35") (name "Net-(U3-SET)") (class "Default")
      (node (ref "R12") (pin "2") (pinfunction "2_2") (pintype "passive"))
      (node (ref "U3") (pin "3") (pinfunction "SET_3") (pintype "input"))
    )
    (net (code "36") (name "Net-(U4-IN)") (class "Default")
      (node (ref "C26") (pin "2") (pinfunction "2_2") (pintype "passive"))
      (node (ref "U4") (pin "2") (pinfunction "IN_2") (pintype "input"))
    )
    (net (code "37") (name "Net-(U4-OUT)") (class "Default")
      (node (ref "C28") (pin "1") (pinfunction "1_1") (pintype "passive"))
      (node (ref "L4") (pin "1") (pinfunction "1_1") (pintype "bidirectional"))
      (node (ref "U4") (pin "7") (pinfunction "OUT_7") (pintype "output"))
    )
    (net (code "38") (name "Net-(U4-SHTDN)") (class "Default")
      (node (ref "R30") (pin "1") (pinfunction "1_1") (pintype "passive"))
      (node (ref "R31") (pin "1") (pinfunction "1_1") (pintype "passive"))
      (node (ref "U4") (pin "6") (pinfunction "SHTDN_6") (pintype "input"))
      (node (ref "U5") (pin "6") (pinfunction "SHTDN_6") (pintype "input"))
    )
    (net (code "39") (name "Net-(U5-IN)") (class "Default")
      (node (ref "C1") (pin "2") (pinfunction "2_2") (pintype "passive"))
      (node (ref "U5") (pin "2") (pinfunction "IN_2") (pintype "input"))
    )
    (net (code "40") (name "Net-(U5-OUT)") (class "Default")
      (node (ref "C3") (pin "1") (pinfunction "1_1") (pintype "passive"))
      (node (ref "L5") (pin "1") (pinfunction "1_1") (pintype "bidirectional"))
      (node (ref "U5") (pin "7") (pinfunction "OUT_7") (pintype "output"))
    )
    (net (code "41") (name "Net-(U7-CTRL)") (class "Default")
      (node (ref "C11") (pin "1") (pinfunction "1_1") (pintype "passive"))
      (node (ref "R21") (pin "2") (pinfunction "2_2") (pintype "passive"))
      (node (ref "R22") (pin "1") (pinfunction "1_1") (pintype "passive"))
      (node (ref "U7") (pin "5") (pinfunction "CTRL_5") (pintype "bidirectional"))
    )
    (net (code "42") (name "Net-(U7-EN)") (class "Default")
      (node (ref "C12") (pin "1") (pinfunction "1_1") (pintype "passive"))
      (node (ref "R15") (pin "2") (pinfunction "2_2") (pintype "passive"))
      (node (ref "R16") (pin "1") (pinfunction "1_1") (pintype "passive"))
      (node (ref "U7") (pin "6") (pinfunction "EN_6") (pintype "bidirectional"))
    )
    (net (code "43") (name "Net-(U8-CTRL)") (class "Default")
      (node (ref "C32") (pin "1") (pinfunction "1_1") (pintype "passive"))
      (node (ref "R26") (pin "2") (pinfunction "2_2") (pintype "passive"))
      (node (ref "R27") (pin "1") (pinfunction "1_1") (pintype "passive"))
      (node (ref "U8") (pin "5") (pinfunction "CTRL_5") (pintype "bidirectional"))
    )
    (net (code "44") (name "Net-(U8-EN)") (class "Default")
      (node (ref "C33") (pin "1") (pinfunction "1_1") (pintype "passive"))
      (node (ref "R24") (pin "2") (pinfunction "2_2") (pintype "passive"))
      (node (ref "R25") (pin "1") (pinfunction "1_1") (pintype "passive"))
      (node (ref "U8") (pin "6") (pinfunction "EN_6") (pintype "bidirectional"))
    )
    (net (code "45") (name "Net-(U10-IREF2)") (class "Default")
      (node (ref "C18") (pin "1") (pinfunction "1_1") (pintype "passive"))
      (node (ref "R19") (pin "2") (pinfunction "2_2") (pintype "passive"))
      (node (ref "U10") (pin "8") (pinfunction "IREF2_8") (pintype "passive"))
    )
    (net (code "46") (name "Net-(U10-VBIAS)") (class "Default")
      (node (ref "R20") (pin "1") (pinfunction "1_1") (pintype "passive"))
      (node (ref "U10") (pin "16") (pinfunction "VBIAS_16") (pintype "power_in"))
    )
    (net (code "47") (name "Net-(U10-VCC1)") (class "Default")
      (node (ref "L2") (pin "1") (pinfunction "1_1") (pintype "bidirectional"))
      (node (ref "U10") (pin "20") (pinfunction "VCC1_20") (pintype "power_in"))
    )
    (net (code "48") (name "Net-(U10-VCC2)") (class "Default")
      (node (ref "L1") (pin "1") (pinfunction "1_1") (pintype "bidirectional"))
      (node (ref "U10") (pin "18") (pinfunction "VCC2_18") (pintype "power_in"))
    )
    (net (code "49") (name "PA_MATCH_OUT") (class "Default")
      (node (ref "C20") (pin "2") (pinfunction "2_2") (pintype "passive"))
      (node (ref "U8") (pin "4") (pinfunction "RF1_4") (pintype "bidirectional"))
    )
    (net (code "50") (name "PA_ON_LNA_OFF") (class "Default")
      (node (ref "R19") (pin "1") (pinfunction "1_1") (pintype "passive"))
      (node (ref "U10") (pin "6") (pinfunction "IREF1_6") (pintype "passive"))
      (node (ref "U12") (pin "1") (pinfunction "A_1") (pintype "input"))
      (node (ref "U2") (pin "6") (pinfunction "OUT_6") (pintype "output"))
    )
    (net (code "51") (name "RX_IN") (class "Default")
      (node (ref "FL1") (pin "1") (pinfunction "IN_1") (pintype "passive"))
      (node (ref "U8") (pin "8") (pinfunction "RF2_8") (pintype "bidirectional"))
    )
    (net (code "52") (name "TX_RX_COMMON") (class "Default")
      (node (ref "U7") (pin "2") (pinfunction "RF_COM_2") (pintype "bidirectional"))
      (node (ref "U8") (pin "2") (pinfunction "RF_COM_2") (pintype "bidirectional"))
    )
    (net (code "53") (name "TX_RX_CTL") (class "Default")
      (node (ref "R26") (pin "1") (pinfunction "1_1") (pintype "passive"))
      (node (ref "U3") (pin "6") (pinfunction "OUT_6") (pintype "output"))
    )
  )
)
